# Controller-Board_Rack-PDU.net
KiCad netlist of a schematic drawn in EAGLE
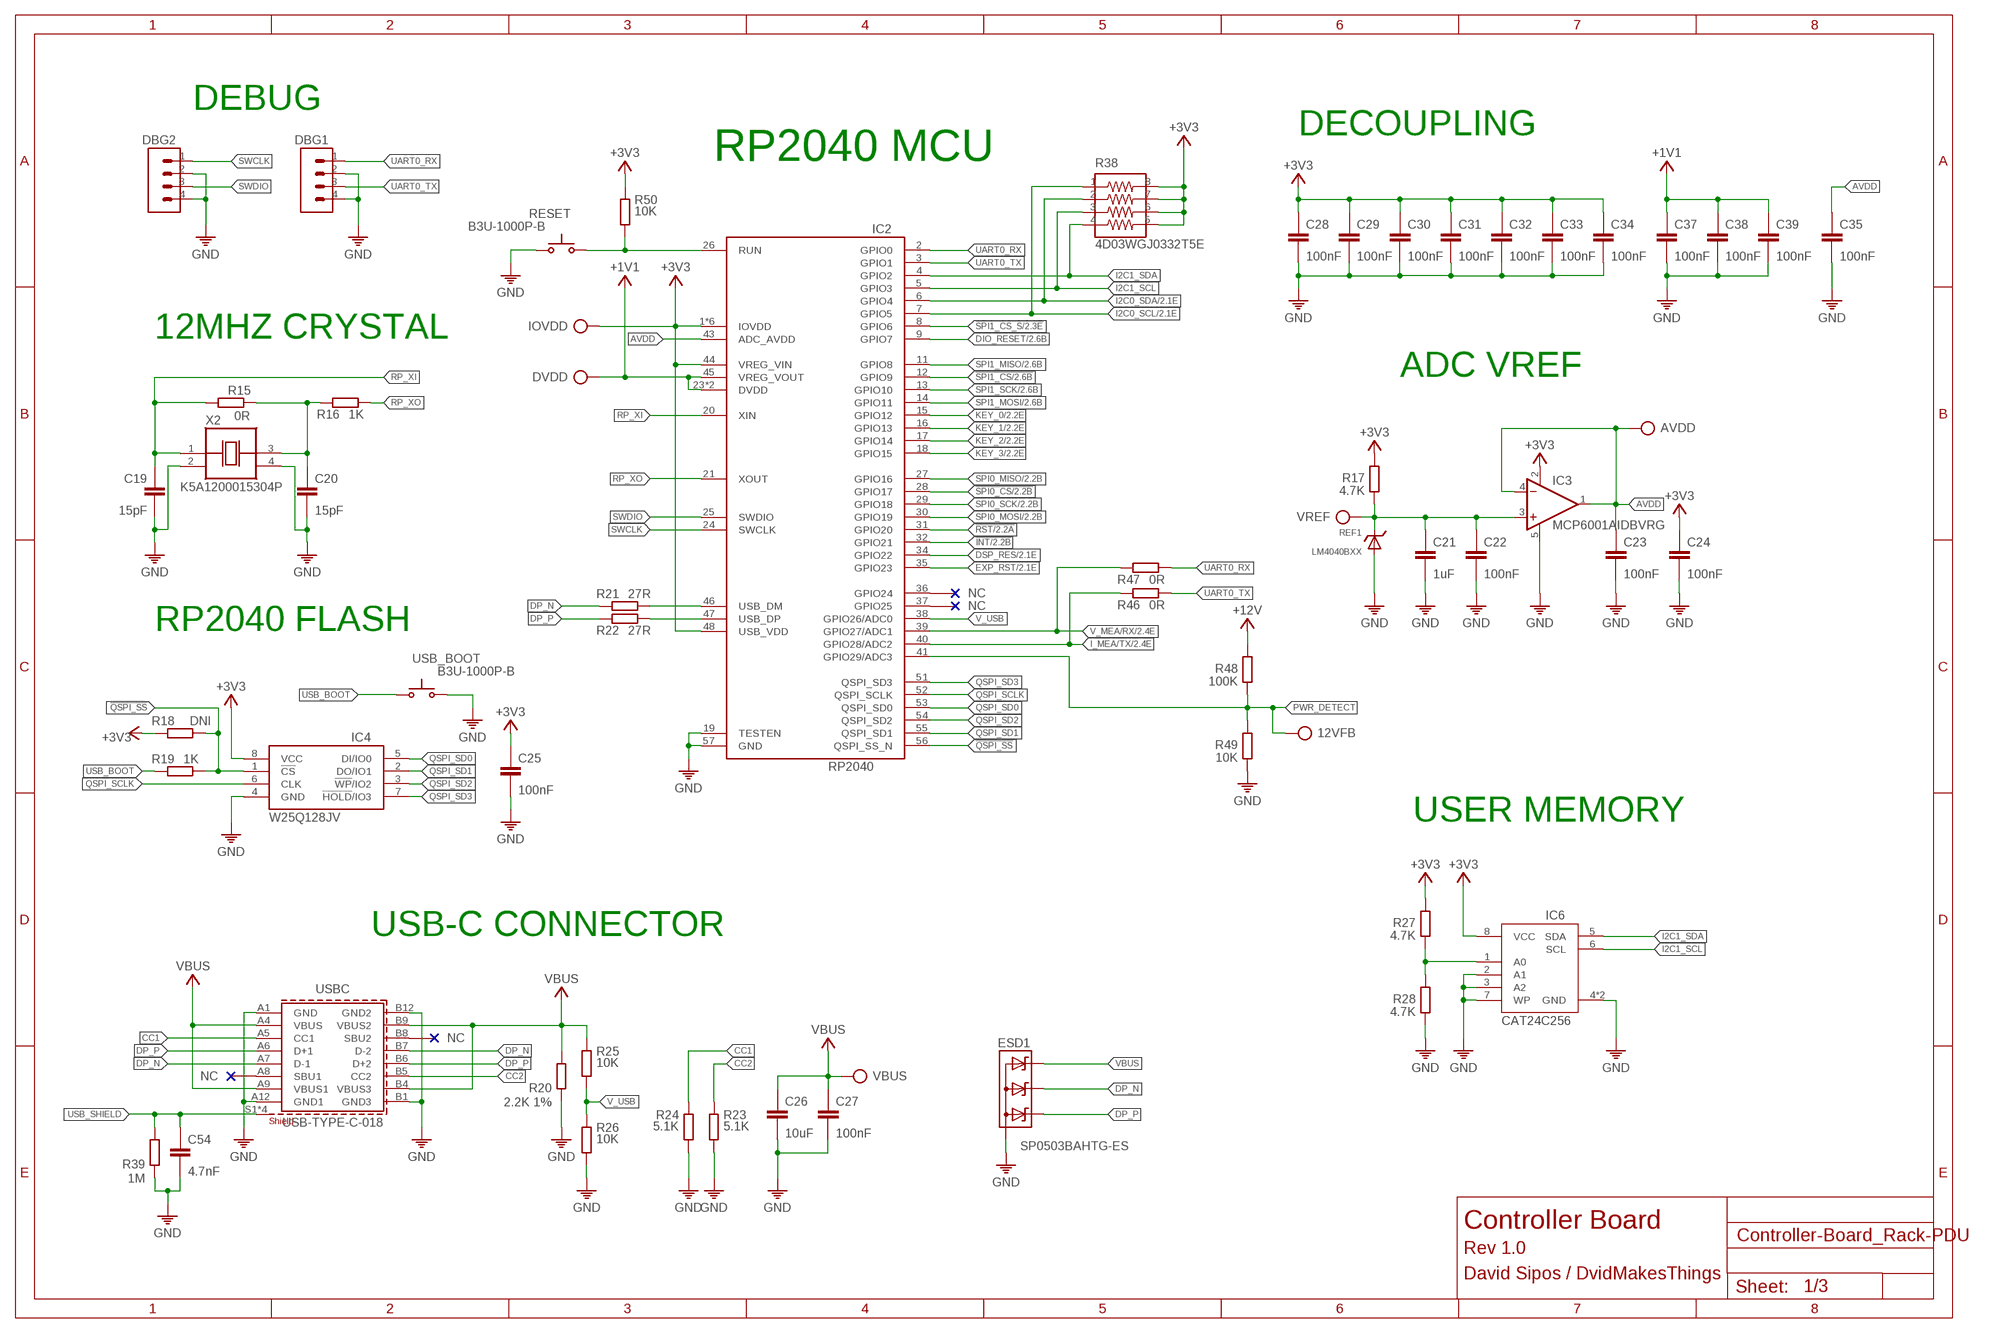
[diagram p0: schematic, sheet 1]
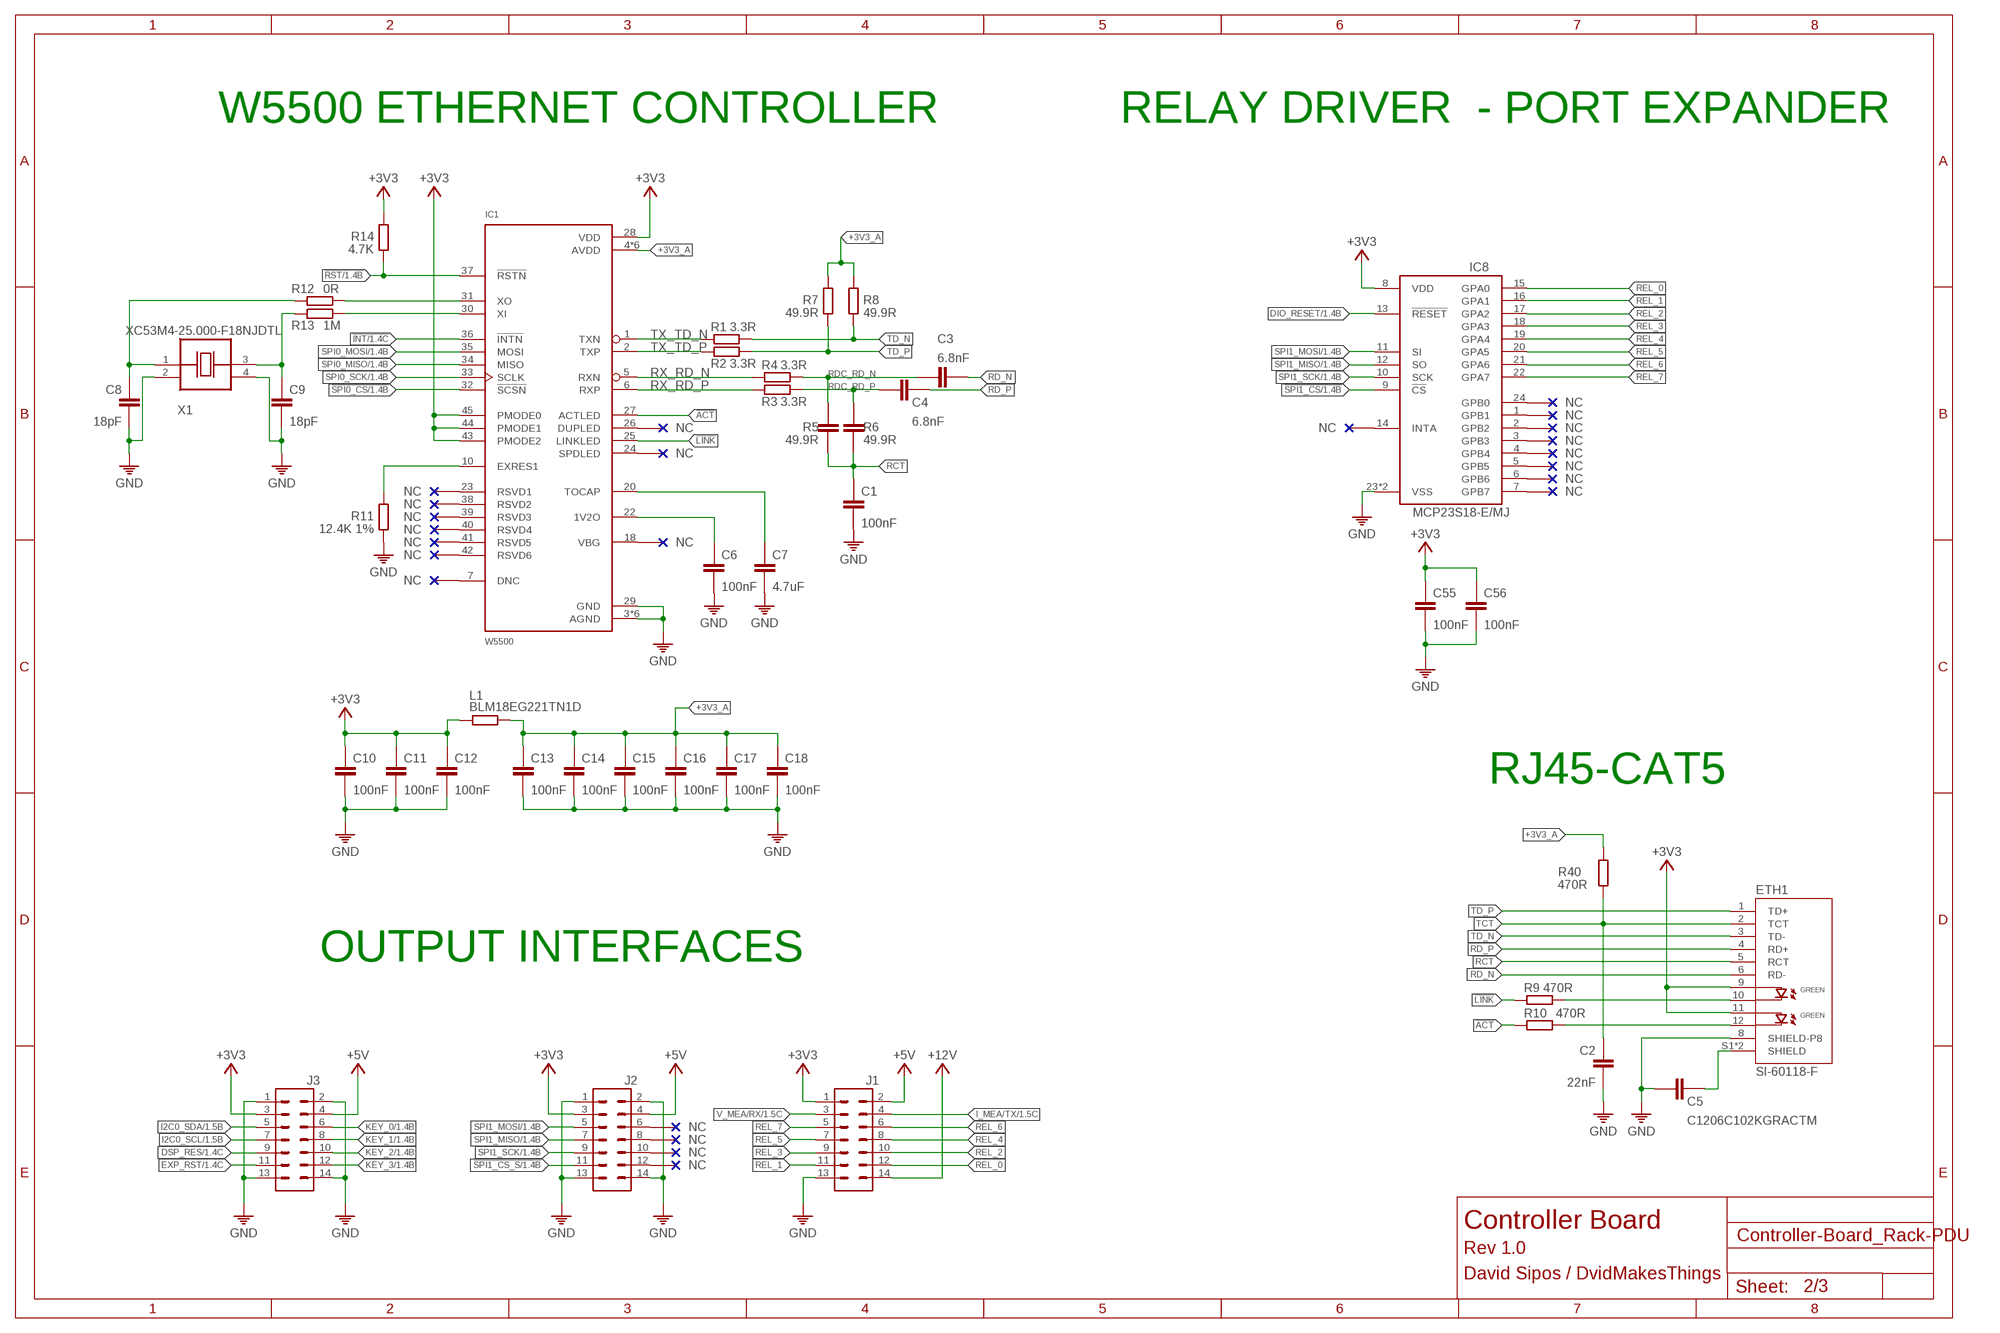
[diagram p1: schematic, sheet 2]
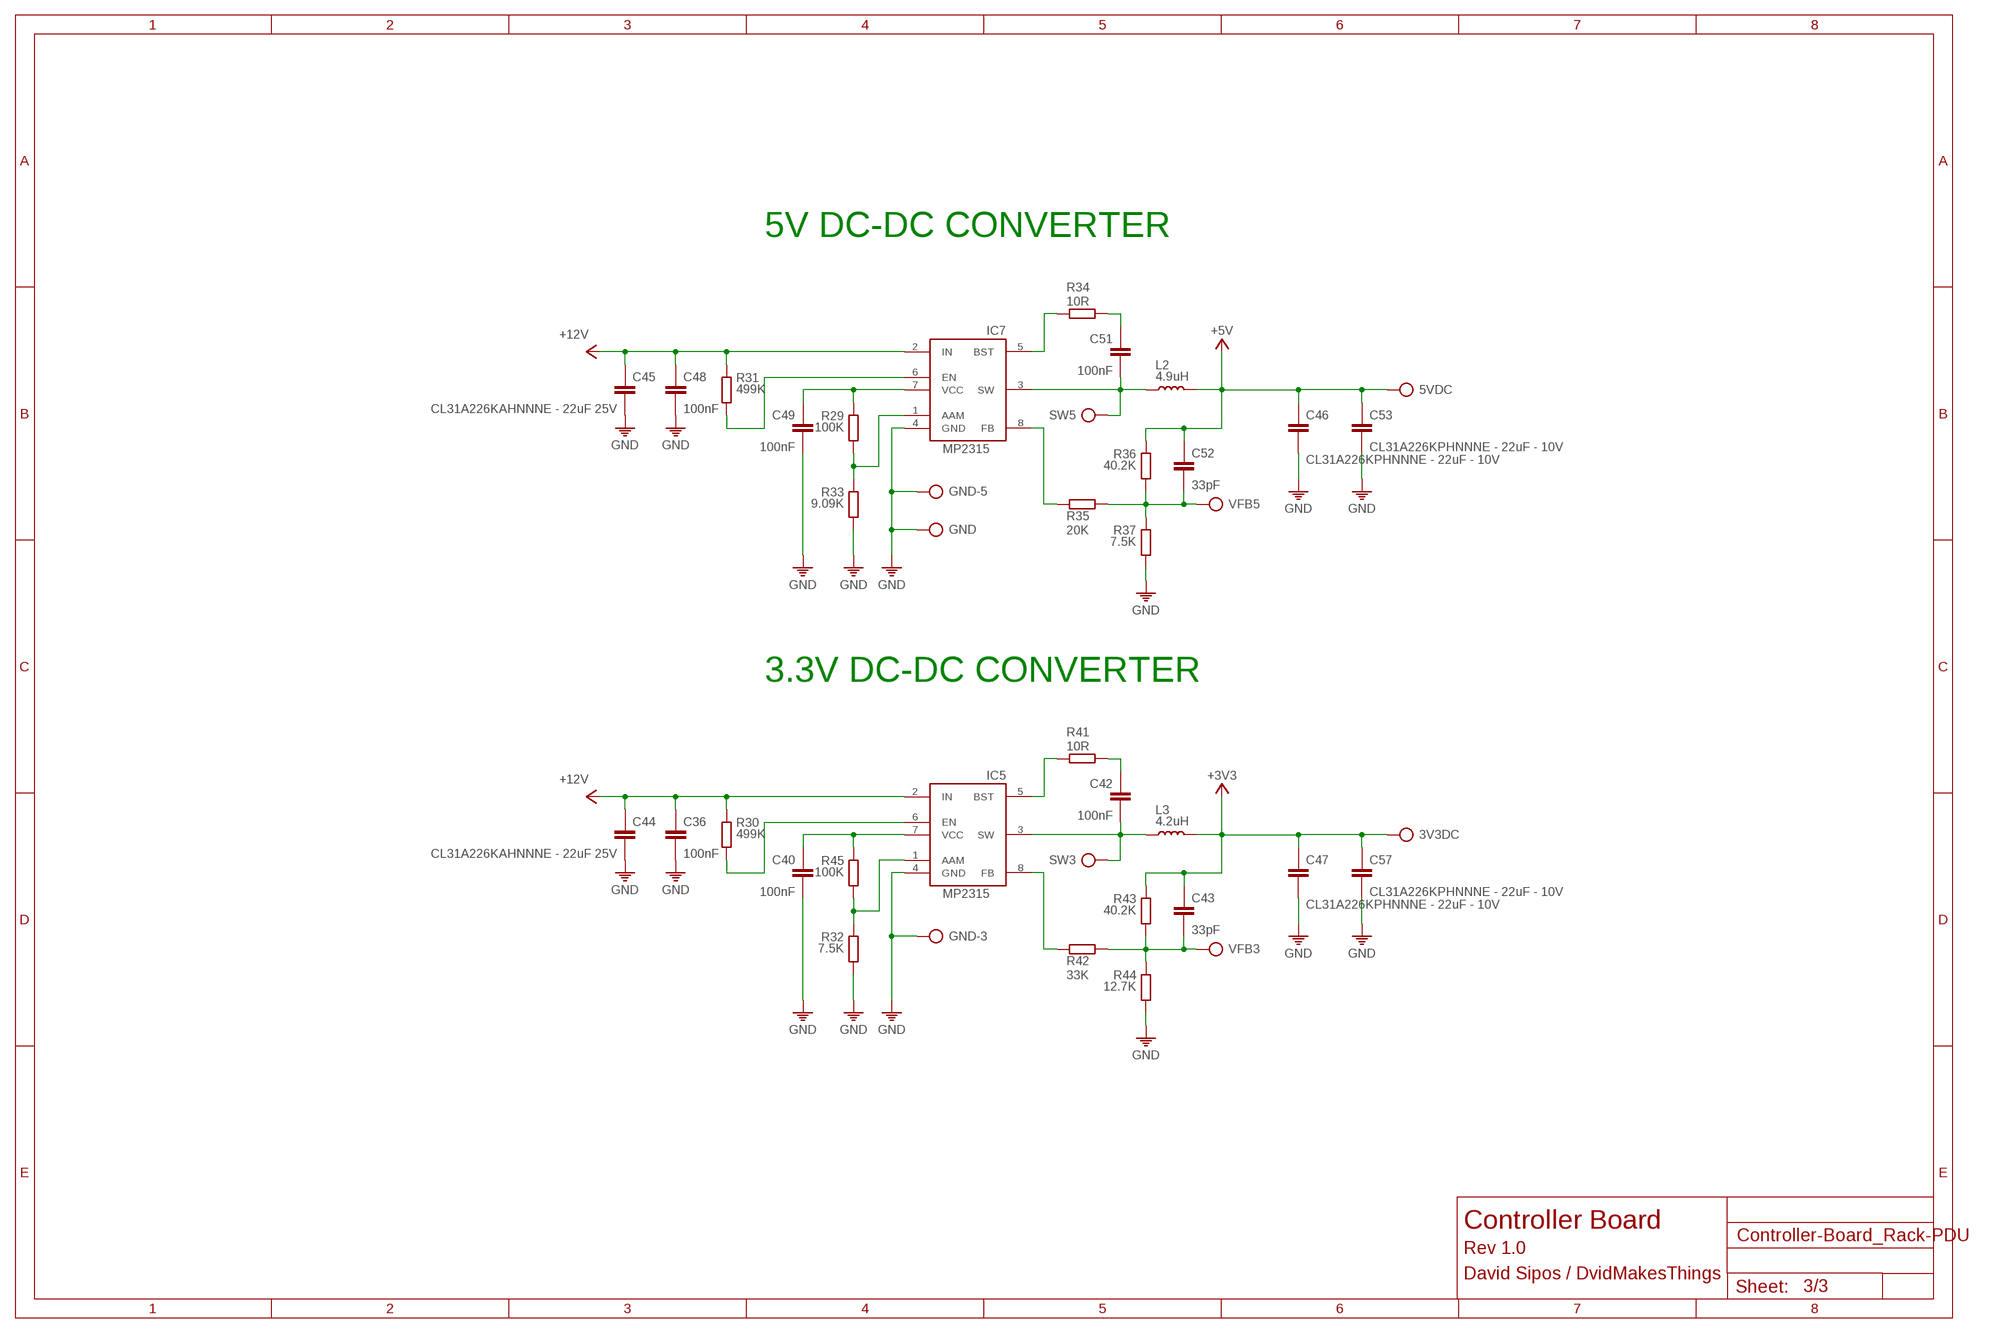
[diagram p2: schematic, sheet 3]

(export (version "E")
  (design (tool "Eeschema 10.0.6"))
  (components
    (comp (ref "12VFB")
      (value "TP")
      (footprint "eagle-import:TP")
      (libsource (lib "eagle-import") (part "TP"))
    )
    (comp (ref "AVDD")
      (value "TP")
      (footprint "eagle-import:TP")
      (libsource (lib "eagle-import") (part "TP"))
    )
    (comp (ref "C19")
      (value "15pF")
      (footprint "eagle-import:C0402")
      (libsource (lib "eagle-import") (part "C-0402"))
    )
    (comp (ref "C20")
      (value "15pF")
      (footprint "eagle-import:C0402")
      (libsource (lib "eagle-import") (part "C-0402"))
    )
    (comp (ref "C21")
      (value "1uF")
      (footprint "eagle-import:C0402")
      (libsource (lib "eagle-import") (part "C-0402"))
    )
    (comp (ref "C22")
      (value "100nF")
      (footprint "eagle-import:C0402")
      (libsource (lib "eagle-import") (part "C-0402"))
    )
    (comp (ref "C23")
      (value "100nF")
      (footprint "eagle-import:C0402")
      (libsource (lib "eagle-import") (part "C-0402"))
    )
    (comp (ref "C24")
      (value "100nF")
      (footprint "eagle-import:C0402")
      (libsource (lib "eagle-import") (part "C-0402"))
    )
    (comp (ref "C25")
      (value "100nF")
      (footprint "eagle-import:C0402")
      (libsource (lib "eagle-import") (part "C-0402"))
    )
    (comp (ref "C26")
      (value "10uF")
      (footprint "eagle-import:0805")
      (libsource (lib "eagle-import") (part "C0805"))
    )
    (comp (ref "C27")
      (value "100nF")
      (footprint "eagle-import:0402")
      (libsource (lib "eagle-import") (part "C0402"))
    )
    (comp (ref "C28")
      (value "100nF")
      (footprint "eagle-import:C0402")
      (libsource (lib "eagle-import") (part "C-0402"))
    )
    (comp (ref "C29")
      (value "100nF")
      (footprint "eagle-import:C0402")
      (libsource (lib "eagle-import") (part "C-0402"))
    )
    (comp (ref "C30")
      (value "100nF")
      (footprint "eagle-import:C0402")
      (libsource (lib "eagle-import") (part "C-0402"))
    )
    (comp (ref "C31")
      (value "100nF")
      (footprint "eagle-import:C0402")
      (libsource (lib "eagle-import") (part "C-0402"))
    )
    (comp (ref "C32")
      (value "100nF")
      (footprint "eagle-import:C0402")
      (libsource (lib "eagle-import") (part "C-0402"))
    )
    (comp (ref "C33")
      (value "100nF")
      (footprint "eagle-import:C0402")
      (libsource (lib "eagle-import") (part "C-0402"))
    )
    (comp (ref "C34")
      (value "100nF")
      (footprint "eagle-import:C0402")
      (libsource (lib "eagle-import") (part "C-0402"))
    )
    (comp (ref "C35")
      (value "100nF")
      (footprint "eagle-import:C0402")
      (libsource (lib "eagle-import") (part "C-0402"))
    )
    (comp (ref "C37")
      (value "100nF")
      (footprint "eagle-import:C0402")
      (libsource (lib "eagle-import") (part "C-0402"))
    )
    (comp (ref "C38")
      (value "100nF")
      (footprint "eagle-import:C0402")
      (libsource (lib "eagle-import") (part "C-0402"))
    )
    (comp (ref "C39")
      (value "100nF")
      (footprint "eagle-import:C0402")
      (libsource (lib "eagle-import") (part "C-0402"))
    )
    (comp (ref "C54")
      (value "4.7nF")
      (footprint "eagle-import:0402")
      (libsource (lib "eagle-import") (part "C0402"))
    )
    (comp (ref "DBG1")
      (value "CON-1X4")
      (footprint "eagle-import:1X4")
      (libsource (lib "eagle-import") (part "CON-1X4"))
    )
    (comp (ref "DBG2")
      (value "CON-1X4")
      (footprint "eagle-import:1X4")
      (libsource (lib "eagle-import") (part "CON-1X4"))
    )
    (comp (ref "DVDD")
      (value "TP")
      (footprint "eagle-import:TP")
      (libsource (lib "eagle-import") (part "TP"))
    )
    (comp (ref "ESD1")
      (value "SP0503BAHTG-ES")
      (footprint "eagle-import:SOT143")
      (libsource (lib "eagle-import") (part "SP0503BAHT"))
    )
    (comp (ref "IC2")
      (value "RP2040")
      (footprint "eagle-import:QFN40P700X700X100-57T510")
      (libsource (lib "eagle-import") (part "RP2040"))
    )
    (comp (ref "IC3")
      (value "MCP6001AIDBVRG")
      (footprint "eagle-import:SOT23-5")
      (libsource (lib "eagle-import") (part "MCP6001RT"))
    )
    (comp (ref "IC4")
      (value "W25Q128JVPIQ")
      (footprint "eagle-import:SON127P600X500X75-8N")
      (libsource (lib "eagle-import") (part "W25Q128JVP"))
    )
    (comp (ref "IC6")
      (value "CAT24C256HU4IGT3")
      (footprint "eagle-import:SON50P300X200X50-9T130X140N")
      (libsource (lib "eagle-import") (part "CAT24C256-HU4"))
    )
    (comp (ref "IOVDD")
      (value "TP")
      (footprint "eagle-import:TP")
      (libsource (lib "eagle-import") (part "TP"))
    )
    (comp (ref "R15")
      (value "0R")
      (footprint "eagle-import:0402")
      (libsource (lib "eagle-import") (part "R0402"))
    )
    (comp (ref "R16")
      (value "1K")
      (footprint "eagle-import:0402")
      (libsource (lib "eagle-import") (part "R0402"))
    )
    (comp (ref "R17")
      (value "4.7K")
      (footprint "eagle-import:0402")
      (libsource (lib "eagle-import") (part "R0402"))
    )
    (comp (ref "R18")
      (value "DNI")
      (footprint "eagle-import:0402")
      (libsource (lib "eagle-import") (part "R0402"))
    )
    (comp (ref "R19")
      (value "1K")
      (footprint "eagle-import:0402")
      (libsource (lib "eagle-import") (part "R0402"))
    )
    (comp (ref "R20")
      (value "2.2K 1%")
      (footprint "eagle-import:0402")
      (libsource (lib "eagle-import") (part "ds_passive_46685041_R0402"))
    )
    (comp (ref "R21")
      (value "27R")
      (footprint "eagle-import:0402")
      (libsource (lib "eagle-import") (part "R0402"))
    )
    (comp (ref "R22")
      (value "27R")
      (footprint "eagle-import:0402")
      (libsource (lib "eagle-import") (part "R0402"))
    )
    (comp (ref "R23")
      (value "5.1K")
      (footprint "eagle-import:0402")
      (libsource (lib "eagle-import") (part "ds_passive_46685041_R0402"))
    )
    (comp (ref "R24")
      (value "5.1K")
      (footprint "eagle-import:0402")
      (libsource (lib "eagle-import") (part "ds_passive_46685041_R0402"))
    )
    (comp (ref "R25")
      (value "10K")
      (footprint "eagle-import:0402")
      (libsource (lib "eagle-import") (part "ds_passive_46685041_R0402"))
    )
    (comp (ref "R26")
      (value "10K")
      (footprint "eagle-import:0402")
      (libsource (lib "eagle-import") (part "ds_passive_46685041_R0402"))
    )
    (comp (ref "R27")
      (value "4.7K")
      (footprint "eagle-import:0402")
      (libsource (lib "eagle-import") (part "R0402"))
    )
    (comp (ref "R28")
      (value "4.7K")
      (footprint "eagle-import:0402")
      (libsource (lib "eagle-import") (part "R0402"))
    )
    (comp (ref "R38")
      (value "4D03WGJ0332T5E")
      (footprint "eagle-import:742C083103JP")
      (fields
        (field (name "MANUFACTURER") "CTS Resistor Products")
        (field (name "MPN") "742C083103JP")
        (field (name "CREATED_BY") "PCBLayout.com")
      )
      (libsource (lib "eagle-import") (part "742C083103JP"))
    )
    (comp (ref "R39")
      (value "1M")
      (footprint "eagle-import:0402")
      (libsource (lib "eagle-import") (part "ds_passive_46685041_R0402"))
    )
    (comp (ref "R46")
      (value "0R")
      (footprint "eagle-import:0402")
      (libsource (lib "eagle-import") (part "R0402"))
    )
    (comp (ref "R47")
      (value "0R")
      (footprint "eagle-import:0402")
      (libsource (lib "eagle-import") (part "R0402"))
    )
    (comp (ref "R48")
      (value "100K")
      (footprint "eagle-import:0402")
      (libsource (lib "eagle-import") (part "R0402"))
    )
    (comp (ref "R49")
      (value "10K")
      (footprint "eagle-import:0402")
      (libsource (lib "eagle-import") (part "R0402"))
    )
    (comp (ref "R50")
      (value "10K")
      (footprint "eagle-import:0402")
      (libsource (lib "eagle-import") (part "ds_passive_46685041_R0402"))
    )
    (comp (ref "REF1")
      (value "LM4040BXX")
      (footprint "eagle-import:SOT23")
      (libsource (lib "eagle-import") (part "LM4040BXX"))
    )
    (comp (ref "RESET")
      (value "B3U-1000P-B")
      (footprint "eagle-import:SWITCH-OMRON_B3U-1000P")
      (libsource (lib "eagle-import") (part "SWITCH-OMRON_B3U-1000P"))
    )
    (comp (ref "USBC")
      (value "USB-TYPE-C-018")
      (footprint "eagle-import:629722000214")
      (libsource (lib "eagle-import") (part "629722000214"))
    )
    (comp (ref "USB_BOOT")
      (value "B3U-1000P-B")
      (footprint "eagle-import:SWITCH-OMRON_B3U-1000P")
      (libsource (lib "eagle-import") (part "SWITCH-OMRON_B3U-1000P"))
    )
    (comp (ref "VBUS")
      (value "TP")
      (footprint "eagle-import:TP")
      (libsource (lib "eagle-import") (part "TP"))
    )
    (comp (ref "VREF")
      (value "TP")
      (footprint "eagle-import:TP")
      (libsource (lib "eagle-import") (part "TP"))
    )
    (comp (ref "X2")
      (value "K5A1200015304P")
      (footprint "eagle-import:OSCCC500X320X130")
      (libsource (lib "eagle-import") (part "CRYSTAL"))
    )
    (comp (ref "3V3DC")
      (value "TP")
      (footprint "eagle-import:TP")
      (libsource (lib "eagle-import") (part "TP"))
    )
    (comp (ref "5VDC")
      (value "TP")
      (footprint "eagle-import:TP")
      (libsource (lib "eagle-import") (part "TP"))
    )
    (comp (ref "C36")
      (value "100nF")
      (footprint "eagle-import:0402")
      (libsource (lib "eagle-import") (part "C0402"))
    )
    (comp (ref "C40")
      (value "100nF")
      (footprint "eagle-import:0402")
      (libsource (lib "eagle-import") (part "C0402"))
    )
    (comp (ref "C42")
      (value "100nF")
      (footprint "eagle-import:0402")
      (libsource (lib "eagle-import") (part "C0402"))
    )
    (comp (ref "C43")
      (value "33pF")
      (footprint "eagle-import:0402")
      (libsource (lib "eagle-import") (part "C0402"))
    )
    (comp (ref "C44")
      (value "CL31A226KAHNNNE - 22uF 25V")
      (footprint "eagle-import:C1206")
      (libsource (lib "eagle-import") (part "C-1206"))
    )
    (comp (ref "C45")
      (value "CL31A226KAHNNNE - 22uF 25V")
      (footprint "eagle-import:C1206")
      (libsource (lib "eagle-import") (part "C-1206"))
    )
    (comp (ref "C46")
      (value "CL31A226KPHNNNE - 22uF - 10V")
      (footprint "eagle-import:C1206")
      (libsource (lib "eagle-import") (part "C-1206"))
    )
    (comp (ref "C47")
      (value "CL31A226KPHNNNE - 22uF - 10V")
      (footprint "eagle-import:C1206")
      (libsource (lib "eagle-import") (part "C-1206"))
    )
    (comp (ref "C48")
      (value "100nF")
      (footprint "eagle-import:0402")
      (libsource (lib "eagle-import") (part "C0402"))
    )
    (comp (ref "C49")
      (value "100nF")
      (footprint "eagle-import:0402")
      (libsource (lib "eagle-import") (part "C0402"))
    )
    (comp (ref "C51")
      (value "100nF")
      (footprint "eagle-import:0402")
      (libsource (lib "eagle-import") (part "C0402"))
    )
    (comp (ref "C52")
      (value "33pF")
      (footprint "eagle-import:0402")
      (libsource (lib "eagle-import") (part "C0402"))
    )
    (comp (ref "C53")
      (value "CL31A226KPHNNNE - 22uF - 10V")
      (footprint "eagle-import:C1206")
      (libsource (lib "eagle-import") (part "C-1206"))
    )
    (comp (ref "C57")
      (value "CL31A226KPHNNNE - 22uF - 10V")
      (footprint "eagle-import:C1206")
      (libsource (lib "eagle-import") (part "C-1206"))
    )
    (comp (ref "GND") (value "TP") (footprint "eagle-import:TP") (libsource (lib "eagle-import") (part "TP")))
    (comp (ref "GND-3")
      (value "TP")
      (footprint "eagle-import:TP")
      (libsource (lib "eagle-import") (part "TP"))
    )
    (comp (ref "GND-5")
      (value "TP")
      (footprint "eagle-import:TP")
      (libsource (lib "eagle-import") (part "TP"))
    )
    (comp (ref "IC5")
      (value "MP2315S")
      (footprint "eagle-import:SOT65P280X110-8N")
      (libsource (lib "eagle-import") (part "MP2315TSOT23-8"))
    )
    (comp (ref "IC7")
      (value "MP2315GJ-Z")
      (footprint "eagle-import:SOT65P280X110-8N")
      (libsource (lib "eagle-import") (part "MP2315TSOT23-8"))
    )
    (comp (ref "L2")
      (value "4.9uH")
      (footprint "eagle-import:SRR5228A")
      (libsource (lib "eagle-import") (part "L"))
    )
    (comp (ref "L3")
      (value "4.2uH")
      (footprint "eagle-import:SRR5228A")
      (libsource (lib "eagle-import") (part "L"))
    )
    (comp (ref "R29")
      (value "100K")
      (footprint "eagle-import:0402")
      (libsource (lib "eagle-import") (part "R0402"))
    )
    (comp (ref "R30")
      (value "499K")
      (footprint "eagle-import:0402")
      (libsource (lib "eagle-import") (part "R0402"))
    )
    (comp (ref "R31")
      (value "499K")
      (footprint "eagle-import:0402")
      (libsource (lib "eagle-import") (part "R0402"))
    )
    (comp (ref "R32")
      (value "7.5K")
      (footprint "eagle-import:0402")
      (libsource (lib "eagle-import") (part "R0402"))
    )
    (comp (ref "R33")
      (value "9.09K")
      (footprint "eagle-import:0402")
      (libsource (lib "eagle-import") (part "R0402"))
    )
    (comp (ref "R34")
      (value "10R")
      (footprint "eagle-import:0402")
      (libsource (lib "eagle-import") (part "R0402"))
    )
    (comp (ref "R35")
      (value "20K")
      (footprint "eagle-import:0402")
      (libsource (lib "eagle-import") (part "R0402"))
    )
    (comp (ref "R36")
      (value "40.2K")
      (footprint "eagle-import:0402")
      (libsource (lib "eagle-import") (part "R0402"))
    )
    (comp (ref "R37")
      (value "7.5K")
      (footprint "eagle-import:0402")
      (libsource (lib "eagle-import") (part "R0402"))
    )
    (comp (ref "R41")
      (value "10R")
      (footprint "eagle-import:0402")
      (libsource (lib "eagle-import") (part "R0402"))
    )
    (comp (ref "R42")
      (value "33K")
      (footprint "eagle-import:0402")
      (libsource (lib "eagle-import") (part "R0402"))
    )
    (comp (ref "R43")
      (value "40.2K")
      (footprint "eagle-import:0402")
      (libsource (lib "eagle-import") (part "R0402"))
    )
    (comp (ref "R44")
      (value "12.7K")
      (footprint "eagle-import:0402")
      (libsource (lib "eagle-import") (part "R0402"))
    )
    (comp (ref "R45")
      (value "100K")
      (footprint "eagle-import:0402")
      (libsource (lib "eagle-import") (part "R0402"))
    )
    (comp (ref "SW3") (value "TP") (footprint "eagle-import:TP") (libsource (lib "eagle-import") (part "TP")))
    (comp (ref "SW5") (value "TP") (footprint "eagle-import:TP") (libsource (lib "eagle-import") (part "TP")))
    (comp (ref "VFB3")
      (value "TP")
      (footprint "eagle-import:TP")
      (libsource (lib "eagle-import") (part "TP"))
    )
    (comp (ref "VFB5")
      (value "TP")
      (footprint "eagle-import:TP")
      (libsource (lib "eagle-import") (part "TP"))
    )
    (comp (ref "C1")
      (value "100nF")
      (footprint "eagle-import:C0402")
      (libsource (lib "eagle-import") (part "C-0402"))
    )
    (comp (ref "C2")
      (value "22nF")
      (footprint "eagle-import:C0402")
      (libsource (lib "eagle-import") (part "C-0402"))
    )
    (comp (ref "C3")
      (value "6.8nF")
      (footprint "eagle-import:C0402")
      (libsource (lib "eagle-import") (part "C-0402"))
    )
    (comp (ref "C4")
      (value "6.8nF")
      (footprint "eagle-import:C0402")
      (libsource (lib "eagle-import") (part "C-0402"))
    )
    (comp (ref "C5")
      (value "C1206C102KGRACTM")
      (footprint "eagle-import:C1206")
      (libsource (lib "eagle-import") (part "C-1206"))
    )
    (comp (ref "C6")
      (value "100nF")
      (footprint "eagle-import:C0402")
      (libsource (lib "eagle-import") (part "C-0402"))
    )
    (comp (ref "C7")
      (value "4.7uF")
      (footprint "eagle-import:C0402")
      (libsource (lib "eagle-import") (part "C-0402"))
    )
    (comp (ref "C8")
      (value "18pF")
      (footprint "eagle-import:C0402")
      (libsource (lib "eagle-import") (part "C-0402"))
    )
    (comp (ref "C9")
      (value "18pF")
      (footprint "eagle-import:C0402")
      (libsource (lib "eagle-import") (part "C-0402"))
    )
    (comp (ref "C10")
      (value "100nF")
      (footprint "eagle-import:C0402")
      (libsource (lib "eagle-import") (part "C-0402"))
    )
    (comp (ref "C11")
      (value "100nF")
      (footprint "eagle-import:C0402")
      (libsource (lib "eagle-import") (part "C-0402"))
    )
    (comp (ref "C12")
      (value "100nF")
      (footprint "eagle-import:C0402")
      (libsource (lib "eagle-import") (part "C-0402"))
    )
    (comp (ref "C13")
      (value "100nF")
      (footprint "eagle-import:C0402")
      (libsource (lib "eagle-import") (part "C-0402"))
    )
    (comp (ref "C14")
      (value "100nF")
      (footprint "eagle-import:C0402")
      (libsource (lib "eagle-import") (part "C-0402"))
    )
    (comp (ref "C15")
      (value "100nF")
      (footprint "eagle-import:C0402")
      (libsource (lib "eagle-import") (part "C-0402"))
    )
    (comp (ref "C16")
      (value "100nF")
      (footprint "eagle-import:C0402")
      (libsource (lib "eagle-import") (part "C-0402"))
    )
    (comp (ref "C17")
      (value "100nF")
      (footprint "eagle-import:C0402")
      (libsource (lib "eagle-import") (part "C-0402"))
    )
    (comp (ref "C18")
      (value "100nF")
      (footprint "eagle-import:C0402")
      (libsource (lib "eagle-import") (part "C-0402"))
    )
    (comp (ref "C55")
      (value "100nF")
      (footprint "eagle-import:C0402")
      (libsource (lib "eagle-import") (part "C-0402"))
    )
    (comp (ref "C56")
      (value "100nF")
      (footprint "eagle-import:C0402")
      (libsource (lib "eagle-import") (part "C-0402"))
    )
    (comp (ref "ETH1")
      (value "SI-60118-F")
      (footprint "eagle-import:RJ45-CAT5")
      (fields (field (name "MANUFACTURER") "Bel Fuse"))
      (libsource (lib "eagle-import") (part "RJ45-CAT5"))
    )
    (comp (ref "IC1")
      (value "W5500")
      (footprint "eagle-import:LQFP48")
      (libsource (lib "eagle-import") (part "W5500"))
    )
    (comp (ref "IC8")
      (value "MCP23S18-E/MJ")
      (footprint "eagle-import:QFN50P400X400X100-25T265")
      (libsource (lib "eagle-import") (part "MCP23S18"))
    )
    (comp (ref "J1")
      (value "CON-2X7")
      (footprint "eagle-import:2X7")
      (libsource (lib "eagle-import") (part "CON-2X7"))
    )
    (comp (ref "J2")
      (value "CON-2X7")
      (footprint "eagle-import:2X7")
      (libsource (lib "eagle-import") (part "CON-2X7"))
    )
    (comp (ref "J3")
      (value "CON-2X7")
      (footprint "eagle-import:2X7")
      (libsource (lib "eagle-import") (part "CON-2X7"))
    )
    (comp (ref "L1")
      (value "BLM18EG221TN1D")
      (footprint "eagle-import:0603")
      (libsource (lib "eagle-import") (part "R0603"))
    )
    (comp (ref "R1")
      (value "3.3R")
      (footprint "eagle-import:0402")
      (libsource (lib "eagle-import") (part "R0402"))
    )
    (comp (ref "R2")
      (value "3.3R")
      (footprint "eagle-import:0402")
      (libsource (lib "eagle-import") (part "R0402"))
    )
    (comp (ref "R3")
      (value "3.3R")
      (footprint "eagle-import:0402")
      (libsource (lib "eagle-import") (part "R0402"))
    )
    (comp (ref "R4")
      (value "3.3R")
      (footprint "eagle-import:0402")
      (libsource (lib "eagle-import") (part "R0402"))
    )
    (comp (ref "R5")
      (value "49.9R")
      (footprint "eagle-import:C0402")
      (libsource (lib "eagle-import") (part "C-0402"))
    )
    (comp (ref "R6")
      (value "49.9R")
      (footprint "eagle-import:C0402")
      (libsource (lib "eagle-import") (part "C-0402"))
    )
    (comp (ref "R7")
      (value "49.9R")
      (footprint "eagle-import:0402")
      (libsource (lib "eagle-import") (part "R0402"))
    )
    (comp (ref "R8")
      (value "49.9R")
      (footprint "eagle-import:0402")
      (libsource (lib "eagle-import") (part "R0402"))
    )
    (comp (ref "R9")
      (value "470R")
      (footprint "eagle-import:0402")
      (libsource (lib "eagle-import") (part "R0402"))
    )
    (comp (ref "R10")
      (value "470R")
      (footprint "eagle-import:0402")
      (libsource (lib "eagle-import") (part "R0402"))
    )
    (comp (ref "R11")
      (value "12.4K 1%")
      (footprint "eagle-import:0402")
      (libsource (lib "eagle-import") (part "R0402"))
    )
    (comp (ref "R12")
      (value "0R")
      (footprint "eagle-import:0402")
      (libsource (lib "eagle-import") (part "R0402"))
    )
    (comp (ref "R13")
      (value "1M")
      (footprint "eagle-import:0402")
      (libsource (lib "eagle-import") (part "R0402"))
    )
    (comp (ref "R14")
      (value "4.7K")
      (footprint "eagle-import:0402")
      (libsource (lib "eagle-import") (part "R0402"))
    )
    (comp (ref "R40")
      (value "470R")
      (footprint "eagle-import:0402")
      (libsource (lib "eagle-import") (part "R0402"))
    )
    (comp (ref "X1")
      (value "XC53M4-25.000-F18NJDTL")
      (footprint "eagle-import:OSCCC500X320X130")
      (libsource (lib "eagle-import") (part "CRYSTAL"))
    )
  )
  (nets
    (net (code "1") (name "+1V1") (class "Default")
      (node (ref "C37") (pin "1") (pinfunction "1_1") (pintype "passive"))
      (node (ref "C38") (pin "1") (pinfunction "1_1") (pintype "passive"))
      (node (ref "C39") (pin "1") (pinfunction "1_1") (pintype "passive"))
      (node (ref "DVDD") (pin "TP") (pinfunction "P$1_TP") (pintype "bidirectional"))
      (node (ref "IC2") (pin "23") (pinfunction "DVDD_23") (pintype "bidirectional"))
      (node (ref "IC2") (pin "45") (pinfunction "VREG_VOUT_45") (pintype "bidirectional"))
      (node (ref "IC2") (pin "50") (pinfunction "DVDD_50") (pintype "bidirectional"))
    )
    (net (code "2") (name "+3V3") (class "Default")
      (node (ref "3V3DC") (pin "TP") (pinfunction "P$1_TP") (pintype "bidirectional"))
      (node (ref "C10") (pin "1") (pinfunction "1_1") (pintype "passive"))
      (node (ref "C11") (pin "1") (pinfunction "1_1") (pintype "passive"))
      (node (ref "C12") (pin "1") (pinfunction "1_1") (pintype "passive"))
      (node (ref "C24") (pin "1") (pinfunction "1_1") (pintype "passive"))
      (node (ref "C25") (pin "1") (pinfunction "1_1") (pintype "passive"))
      (node (ref "C28") (pin "1") (pinfunction "1_1") (pintype "passive"))
      (node (ref "C29") (pin "1") (pinfunction "1_1") (pintype "passive"))
      (node (ref "C30") (pin "1") (pinfunction "1_1") (pintype "passive"))
      (node (ref "C31") (pin "1") (pinfunction "1_1") (pintype "passive"))
      (node (ref "C32") (pin "1") (pinfunction "1_1") (pintype "passive"))
      (node (ref "C33") (pin "1") (pinfunction "1_1") (pintype "passive"))
      (node (ref "C34") (pin "1") (pinfunction "1_1") (pintype "passive"))
      (node (ref "C43") (pin "1") (pinfunction "1_1") (pintype "passive"))
      (node (ref "C47") (pin "1") (pinfunction "1_1") (pintype "passive"))
      (node (ref "C55") (pin "1") (pinfunction "1_1") (pintype "passive"))
      (node (ref "C56") (pin "1") (pinfunction "1_1") (pintype "passive"))
      (node (ref "C57") (pin "1") (pinfunction "1_1") (pintype "passive"))
      (node (ref "ETH1") (pin "11") (pinfunction "GA2_11") (pintype "passive"))
      (node (ref "ETH1") (pin "9") (pinfunction "GA1_9") (pintype "passive"))
      (node (ref "IC1") (pin "28") (pinfunction "VDD_28") (pintype "power_in"))
      (node (ref "IC1") (pin "43") (pinfunction "PMODE2_43") (pintype "input"))
      (node (ref "IC1") (pin "44") (pinfunction "PMODE1_44") (pintype "input"))
      (node (ref "IC1") (pin "45") (pinfunction "PMODE0_45") (pintype "input"))
      (node (ref "IC2") (pin "1") (pinfunction "IOVDD_1") (pintype "bidirectional"))
      (node (ref "IC2") (pin "10") (pinfunction "IOVDD_10") (pintype "bidirectional"))
      (node (ref "IC2") (pin "22") (pinfunction "IOVDD_22") (pintype "bidirectional"))
      (node (ref "IC2") (pin "33") (pinfunction "IOVDD_33") (pintype "bidirectional"))
      (node (ref "IC2") (pin "42") (pinfunction "IOVDD_42") (pintype "bidirectional"))
      (node (ref "IC2") (pin "44") (pinfunction "VREG_VIN_44") (pintype "bidirectional"))
      (node (ref "IC2") (pin "48") (pinfunction "USB_VDD_48") (pintype "bidirectional"))
      (node (ref "IC2") (pin "49") (pinfunction "IOVDD_49") (pintype "bidirectional"))
      (node (ref "IC3") (pin "2") (pinfunction "V+_2") (pintype "power_in"))
      (node (ref "IC4") (pin "8") (pinfunction "VCC_8") (pintype "power_in"))
      (node (ref "IC6") (pin "8") (pinfunction "VCC_8") (pintype "power_in"))
      (node (ref "IC8") (pin "8") (pinfunction "VDD_8") (pintype "power_in"))
      (node (ref "IOVDD") (pin "TP") (pinfunction "P$1_TP") (pintype "bidirectional"))
      (node (ref "J1") (pin "1") (pinfunction "1_1") (pintype "bidirectional"))
      (node (ref "J2") (pin "3") (pinfunction "3_3") (pintype "bidirectional"))
      (node (ref "J3") (pin "3") (pinfunction "3_3") (pintype "bidirectional"))
      (node (ref "L1") (pin "1") (pinfunction "1_1") (pintype "passive"))
      (node (ref "L3") (pin "2") (pinfunction "2_2") (pintype "passive"))
      (node (ref "R14") (pin "2") (pinfunction "2_2") (pintype "passive"))
      (node (ref "R17") (pin "2") (pinfunction "2_2") (pintype "passive"))
      (node (ref "R18") (pin "2") (pinfunction "2_2") (pintype "passive"))
      (node (ref "R27") (pin "2") (pinfunction "2_2") (pintype "passive"))
      (node (ref "R38") (pin "5") (pinfunction "5_5") (pintype "passive"))
      (node (ref "R38") (pin "6") (pinfunction "6_6") (pintype "passive"))
      (node (ref "R38") (pin "7") (pinfunction "7_7") (pintype "passive"))
      (node (ref "R38") (pin "8") (pinfunction "8_8") (pintype "passive"))
      (node (ref "R43") (pin "1") (pinfunction "1_1") (pintype "passive"))
      (node (ref "R50") (pin "1") (pinfunction "1_1") (pintype "passive"))
    )
    (net (code "3") (name "+3V3_A") (class "Default")
      (node (ref "C13") (pin "1") (pinfunction "1_1") (pintype "passive"))
      (node (ref "C14") (pin "1") (pinfunction "1_1") (pintype "passive"))
      (node (ref "C15") (pin "1") (pinfunction "1_1") (pintype "passive"))
      (node (ref "C16") (pin "1") (pinfunction "1_1") (pintype "passive"))
      (node (ref "C17") (pin "1") (pinfunction "1_1") (pintype "passive"))
      (node (ref "C18") (pin "1") (pinfunction "1_1") (pintype "passive"))
      (node (ref "IC1") (pin "11") (pinfunction "AVDD_11") (pintype "power_in"))
      (node (ref "IC1") (pin "15") (pinfunction "AVDD_15") (pintype "power_in"))
      (node (ref "IC1") (pin "17") (pinfunction "AVDD_17") (pintype "power_in"))
      (node (ref "IC1") (pin "21") (pinfunction "AVDD_21") (pintype "power_in"))
      (node (ref "IC1") (pin "4") (pinfunction "AVDD_4") (pintype "power_in"))
      (node (ref "IC1") (pin "8") (pinfunction "AVDD_8") (pintype "power_in"))
      (node (ref "L1") (pin "2") (pinfunction "2_2") (pintype "passive"))
      (node (ref "R40") (pin "2") (pinfunction "2_2") (pintype "passive"))
      (node (ref "R7") (pin "2") (pinfunction "2_2") (pintype "passive"))
      (node (ref "R8") (pin "2") (pinfunction "2_2") (pintype "passive"))
    )
    (net (code "4") (name "+5V") (class "Default")
      (node (ref "5VDC") (pin "TP") (pinfunction "P$1_TP") (pintype "bidirectional"))
      (node (ref "C46") (pin "1") (pinfunction "1_1") (pintype "passive"))
      (node (ref "C52") (pin "1") (pinfunction "1_1") (pintype "passive"))
      (node (ref "C53") (pin "1") (pinfunction "1_1") (pintype "passive"))
      (node (ref "J1") (pin "2") (pinfunction "2_2") (pintype "bidirectional"))
      (node (ref "J2") (pin "4") (pinfunction "4_4") (pintype "bidirectional"))
      (node (ref "J3") (pin "4") (pinfunction "4_4") (pintype "bidirectional"))
      (node (ref "L2") (pin "2") (pinfunction "2_2") (pintype "passive"))
      (node (ref "R36") (pin "1") (pinfunction "1_1") (pintype "passive"))
    )
    (net (code "5") (name "+12V") (class "Default")
      (node (ref "C36") (pin "1") (pinfunction "1_1") (pintype "passive"))
      (node (ref "C44") (pin "1") (pinfunction "1_1") (pintype "passive"))
      (node (ref "C45") (pin "1") (pinfunction "1_1") (pintype "passive"))
      (node (ref "C48") (pin "1") (pinfunction "1_1") (pintype "passive"))
      (node (ref "IC5") (pin "2") (pinfunction "IN_2") (pintype "bidirectional"))
      (node (ref "IC7") (pin "2") (pinfunction "IN_2") (pintype "bidirectional"))
      (node (ref "J1") (pin "14") (pinfunction "14_14") (pintype "bidirectional"))
      (node (ref "R30") (pin "1") (pinfunction "1_1") (pintype "passive"))
      (node (ref "R31") (pin "1") (pinfunction "1_1") (pintype "passive"))
      (node (ref "R48") (pin "2") (pinfunction "2_2") (pintype "passive"))
    )
    (net (code "6") (name "AVDD") (class "Default")
      (node (ref "AVDD") (pin "TP") (pinfunction "P$1_TP") (pintype "bidirectional"))
      (node (ref "C23") (pin "1") (pinfunction "1_1") (pintype "passive"))
      (node (ref "C35") (pin "1") (pinfunction "1_1") (pintype "passive"))
      (node (ref "IC2") (pin "43") (pinfunction "ADC_AVDD_43") (pintype "bidirectional"))
      (node (ref "IC3") (pin "1") (pinfunction "OUT_1") (pintype "output"))
      (node (ref "IC3") (pin "4") (pinfunction "-IN_4") (pintype "input"))
    )
    (net (code "7") (name "CC1") (class "Default")
      (node (ref "R24") (pin "1") (pinfunction "1_1") (pintype "passive"))
      (node (ref "USBC") (pin "A5") (pinfunction "CC1_A5") (pintype "passive"))
    )
    (net (code "8") (name "CC2") (class "Default")
      (node (ref "R23") (pin "1") (pinfunction "1_1") (pintype "passive"))
      (node (ref "USBC") (pin "B5") (pinfunction "CC2_B5") (pintype "passive"))
    )
    (net (code "9") (name "DIO_RESET") (class "Default")
      (node (ref "IC2") (pin "9") (pinfunction "GPIO7_9") (pintype "bidirectional"))
      (node (ref "IC8") (pin "13") (pinfunction "~{RESET}_13") (pintype "input"))
    )
    (net (code "10") (name "DP_N") (class "Default")
      (node (ref "ESD1") (pin "3") (pinfunction "C2_3") (pintype "bidirectional"))
      (node (ref "R21") (pin "1") (pinfunction "1_1") (pintype "passive"))
      (node (ref "USBC") (pin "A7") (pinfunction "D-1_A7") (pintype "passive"))
      (node (ref "USBC") (pin "B7") (pinfunction "D-2_B7") (pintype "passive"))
    )
    (net (code "11") (name "DP_P") (class "Default")
      (node (ref "ESD1") (pin "2") (pinfunction "C1_2") (pintype "bidirectional"))
      (node (ref "R22") (pin "1") (pinfunction "1_1") (pintype "passive"))
      (node (ref "USBC") (pin "A6") (pinfunction "D+1_A6") (pintype "passive"))
      (node (ref "USBC") (pin "B6") (pinfunction "D+2_B6") (pintype "passive"))
    )
    (net (code "12") (name "DSP_RES") (class "Default")
      (node (ref "IC2") (pin "34") (pinfunction "GPIO22_34") (pintype "bidirectional"))
      (node (ref "J3") (pin "9") (pinfunction "9_9") (pintype "bidirectional"))
    )
    (net (code "13") (name "EXP_RST") (class "Default")
      (node (ref "IC2") (pin "35") (pinfunction "GPIO23_35") (pintype "bidirectional"))
      (node (ref "J3") (pin "11") (pinfunction "11_11") (pintype "bidirectional"))
    )
    (net (code "14") (name "GND") (class "Default")
      (node (ref "C1") (pin "2") (pinfunction "2_2") (pintype "passive"))
      (node (ref "C10") (pin "2") (pinfunction "2_2") (pintype "passive"))
      (node (ref "C11") (pin "2") (pinfunction "2_2") (pintype "passive"))
      (node (ref "C12") (pin "2") (pinfunction "2_2") (pintype "passive"))
      (node (ref "C13") (pin "2") (pinfunction "2_2") (pintype "passive"))
      (node (ref "C14") (pin "2") (pinfunction "2_2") (pintype "passive"))
      (node (ref "C15") (pin "2") (pinfunction "2_2") (pintype "passive"))
      (node (ref "C16") (pin "2") (pinfunction "2_2") (pintype "passive"))
      (node (ref "C17") (pin "2") (pinfunction "2_2") (pintype "passive"))
      (node (ref "C18") (pin "2") (pinfunction "2_2") (pintype "passive"))
      (node (ref "C19") (pin "2") (pinfunction "2_2") (pintype "passive"))
      (node (ref "C2") (pin "2") (pinfunction "2_2") (pintype "passive"))
      (node (ref "C20") (pin "2") (pinfunction "2_2") (pintype "passive"))
      (node (ref "C21") (pin "2") (pinfunction "2_2") (pintype "passive"))
      (node (ref "C22") (pin "2") (pinfunction "2_2") (pintype "passive"))
      (node (ref "C23") (pin "2") (pinfunction "2_2") (pintype "passive"))
      (node (ref "C24") (pin "2") (pinfunction "2_2") (pintype "passive"))
      (node (ref "C25") (pin "2") (pinfunction "2_2") (pintype "passive"))
      (node (ref "C26") (pin "2") (pinfunction "2_2") (pintype "passive"))
      (node (ref "C27") (pin "2") (pinfunction "2_2") (pintype "passive"))
      (node (ref "C28") (pin "2") (pinfunction "2_2") (pintype "passive"))
      (node (ref "C29") (pin "2") (pinfunction "2_2") (pintype "passive"))
      (node (ref "C30") (pin "2") (pinfunction "2_2") (pintype "passive"))
      (node (ref "C31") (pin "2") (pinfunction "2_2") (pintype "passive"))
      (node (ref "C32") (pin "2") (pinfunction "2_2") (pintype "passive"))
      (node (ref "C33") (pin "2") (pinfunction "2_2") (pintype "passive"))
      (node (ref "C34") (pin "2") (pinfunction "2_2") (pintype "passive"))
      (node (ref "C35") (pin "2") (pinfunction "2_2") (pintype "passive"))
      (node (ref "C36") (pin "2") (pinfunction "2_2") (pintype "passive"))
      (node (ref "C37") (pin "2") (pinfunction "2_2") (pintype "passive"))
      (node (ref "C38") (pin "2") (pinfunction "2_2") (pintype "passive"))
      (node (ref "C39") (pin "2") (pinfunction "2_2") (pintype "passive"))
      (node (ref "C40") (pin "2") (pinfunction "2_2") (pintype "passive"))
      (node (ref "C44") (pin "2") (pinfunction "2_2") (pintype "passive"))
      (node (ref "C45") (pin "2") (pinfunction "2_2") (pintype "passive"))
      (node (ref "C46") (pin "2") (pinfunction "2_2") (pintype "passive"))
      (node (ref "C47") (pin "2") (pinfunction "2_2") (pintype "passive"))
      (node (ref "C48") (pin "2") (pinfunction "2_2") (pintype "passive"))
      (node (ref "C49") (pin "2") (pinfunction "2_2") (pintype "passive"))
      (node (ref "C5") (pin "1") (pinfunction "1_1") (pintype "passive"))
      (node (ref "C53") (pin "2") (pinfunction "2_2") (pintype "passive"))
      (node (ref "C54") (pin "2") (pinfunction "2_2") (pintype "passive"))
      (node (ref "C55") (pin "2") (pinfunction "2_2") (pintype "passive"))
      (node (ref "C56") (pin "2") (pinfunction "2_2") (pintype "passive"))
      (node (ref "C57") (pin "2") (pinfunction "2_2") (pintype "passive"))
      (node (ref "C6") (pin "2") (pinfunction "2_2") (pintype "passive"))
      (node (ref "C7") (pin "2") (pinfunction "2_2") (pintype "passive"))
      (node (ref "C8") (pin "2") (pinfunction "2_2") (pintype "passive"))
      (node (ref "C9") (pin "2") (pinfunction "2_2") (pintype "passive"))
      (node (ref "DBG1") (pin "2") (pinfunction "P$2_2") (pintype "bidirectional"))
      (node (ref "DBG1") (pin "4") (pinfunction "P$4_4") (pintype "bidirectional"))
      (node (ref "DBG2") (pin "2") (pinfunction "P$2_2") (pintype "bidirectional"))
      (node (ref "DBG2") (pin "4") (pinfunction "P$4_4") (pintype "bidirectional"))
      (node (ref "ESD1") (pin "1") (pinfunction "A_1") (pintype "bidirectional"))
      (node (ref "ETH1") (pin "8") (pinfunction "SHIELD-P8_8") (pintype "passive"))
      (node (ref "GND") (pin "TP") (pinfunction "P$1_TP") (pintype "bidirectional"))
      (node (ref "GND-3") (pin "TP") (pinfunction "P$1_TP") (pintype "bidirectional"))
      (node (ref "GND-5") (pin "TP") (pinfunction "P$1_TP") (pintype "bidirectional"))
      (node (ref "IC1") (pin "14") (pinfunction "AGND_14") (pintype "power_in"))
      (node (ref "IC1") (pin "16") (pinfunction "AGND_16") (pintype "power_in"))
      (node (ref "IC1") (pin "19") (pinfunction "AGND_19") (pintype "power_in"))
      (node (ref "IC1") (pin "29") (pinfunction "GND_29") (pintype "passive"))
      (node (ref "IC1") (pin "3") (pinfunction "AGND_3") (pintype "power_in"))
      (node (ref "IC1") (pin "48") (pinfunction "AGND_48") (pintype "power_in"))
      (node (ref "IC1") (pin "9") (pinfunction "AGND_9") (pintype "power_in"))
      (node (ref "IC2") (pin "19") (pinfunction "TESTEN_19") (pintype "bidirectional"))
      (node (ref "IC2") (pin "57") (pinfunction "GND_57") (pintype "bidirectional"))
      (node (ref "IC3") (pin "5") (pinfunction "V-_5") (pintype "power_in"))
      (node (ref "IC4") (pin "4") (pinfunction "GND_4") (pintype "power_in"))
      (node (ref "IC5") (pin "4") (pinfunction "GND_4") (pintype "bidirectional"))
      (node (ref "IC6") (pin "2") (pinfunction "A1_2") (pintype "bidirectional"))
      (node (ref "IC6") (pin "3") (pinfunction "A2_3") (pintype "bidirectional"))
      (node (ref "IC6") (pin "4") (pinfunction "GND_4") (pintype "power_in"))
      (node (ref "IC6") (pin "7") (pinfunction "WP_7") (pintype "bidirectional"))
      (node (ref "IC6") (pin "9") (pinfunction "GND_9") (pintype "power_in"))
      (node (ref "IC7") (pin "4") (pinfunction "GND_4") (pintype "bidirectional"))
      (node (ref "IC8") (pin "23") (pinfunction "VSS_23") (pintype "power_in"))
      (node (ref "IC8") (pin "25") (pinfunction "VSS_25") (pintype "power_in"))
      (node (ref "J1") (pin "13") (pinfunction "13_13") (pintype "bidirectional"))
      (node (ref "J2") (pin "1") (pinfunction "1_1") (pintype "bidirectional"))
      (node (ref "J2") (pin "13") (pinfunction "13_13") (pintype "bidirectional"))
      (node (ref "J2") (pin "14") (pinfunction "14_14") (pintype "bidirectional"))
      (node (ref "J2") (pin "2") (pinfunction "2_2") (pintype "bidirectional"))
      (node (ref "J3") (pin "1") (pinfunction "1_1") (pintype "bidirectional"))
      (node (ref "J3") (pin "13") (pinfunction "13_13") (pintype "bidirectional"))
      (node (ref "J3") (pin "14") (pinfunction "14_14") (pintype "bidirectional"))
      (node (ref "J3") (pin "2") (pinfunction "2_2") (pintype "bidirectional"))
      (node (ref "R11") (pin "1") (pinfunction "1_1") (pintype "passive"))
      (node (ref "R20") (pin "2") (pinfunction "2_2") (pintype "passive"))
      (node (ref "R23") (pin "2") (pinfunction "2_2") (pintype "passive"))
      (node (ref "R24") (pin "2") (pinfunction "2_2") (pintype "passive"))
      (node (ref "R26") (pin "2") (pinfunction "2_2") (pintype "passive"))
      (node (ref "R28") (pin "1") (pinfunction "1_1") (pintype "passive"))
      (node (ref "R32") (pin "2") (pinfunction "2_2") (pintype "passive"))
      (node (ref "R33") (pin "2") (pinfunction "2_2") (pintype "passive"))
      (node (ref "R37") (pin "2") (pinfunction "2_2") (pintype "passive"))
      (node (ref "R39") (pin "2") (pinfunction "2_2") (pintype "passive"))
      (node (ref "R44") (pin "2") (pinfunction "2_2") (pintype "passive"))
      (node (ref "R49") (pin "1") (pinfunction "1_1") (pintype "passive"))
      (node (ref "REF1") (pin "2") (pinfunction "A_2") (pintype "passive"))
      (node (ref "REF1") (pin "3") (pinfunction "A_3") (pintype "passive"))
      (node (ref "RESET") (pin "2") (pinfunction "S_2") (pintype "passive"))
      (node (ref "USBC") (pin "A1") (pinfunction "GND_A1") (pintype "passive"))
      (node (ref "USBC") (pin "A12") (pinfunction "GND1_A12") (pintype "passive"))
      (node (ref "USBC") (pin "B1") (pinfunction "GND3_B1") (pintype "passive"))
      (node (ref "USBC") (pin "B12") (pinfunction "GND2_B12") (pintype "passive"))
      (node (ref "USB_BOOT") (pin "2") (pinfunction "S_2") (pintype "passive"))
      (node (ref "X1") (pin "2") (pinfunction "VSS_2") (pintype "power_in"))
      (node (ref "X1") (pin "4") (pinfunction "VDD_4") (pintype "power_in"))
      (node (ref "X2") (pin "2") (pinfunction "VSS_2") (pintype "power_in"))
      (node (ref "X2") (pin "4") (pinfunction "VDD_4") (pintype "power_in"))
    )
    (net (code "15") (name "I2C0_SCL") (class "Default")
      (node (ref "IC2") (pin "7") (pinfunction "GPIO5_7") (pintype "bidirectional"))
      (node (ref "J3") (pin "7") (pinfunction "7_7") (pintype "bidirectional"))
      (node (ref "R38") (pin "1") (pinfunction "1_1") (pintype "passive"))
    )
    (net (code "16") (name "I2C0_SDA") (class "Default")
      (node (ref "IC2") (pin "6") (pinfunction "GPIO4_6") (pintype "bidirectional"))
      (node (ref "J3") (pin "5") (pinfunction "5_5") (pintype "bidirectional"))
      (node (ref "R38") (pin "2") (pinfunction "2_2") (pintype "passive"))
    )
    (net (code "17") (name "I2C1_SCL") (class "Default")
      (node (ref "IC2") (pin "5") (pinfunction "GPIO3_5") (pintype "bidirectional"))
      (node (ref "IC6") (pin "6") (pinfunction "SCL_6") (pintype "bidirectional"))
      (node (ref "R38") (pin "3") (pinfunction "3_3") (pintype "passive"))
    )
    (net (code "18") (name "I2C1_SDA") (class "Default")
      (node (ref "IC2") (pin "4") (pinfunction "GPIO2_4") (pintype "bidirectional"))
      (node (ref "IC6") (pin "5") (pinfunction "SDA_5") (pintype "bidirectional"))
      (node (ref "R38") (pin "4") (pinfunction "4_4") (pintype "passive"))
    )
    (net (code "19") (name "I_MEA{slash}TX") (class "Default")
      (node (ref "IC2") (pin "40") (pinfunction "GPIO28/ADC2_40") (pintype "bidirectional"))
      (node (ref "J1") (pin "4") (pinfunction "4_4") (pintype "bidirectional"))
      (node (ref "R46") (pin "1") (pinfunction "1_1") (pintype "passive"))
    )
    (net (code "20") (name "KEY_0") (class "Default")
      (node (ref "IC2") (pin "15") (pinfunction "GPIO12_15") (pintype "bidirectional"))
      (node (ref "J3") (pin "6") (pinfunction "6_6") (pintype "bidirectional"))
    )
    (net (code "21") (name "KEY_1") (class "Default")
      (node (ref "IC2") (pin "16") (pinfunction "GPIO13_16") (pintype "bidirectional"))
      (node (ref "J3") (pin "8") (pinfunction "8_8") (pintype "bidirectional"))
    )
    (net (code "22") (name "KEY_2") (class "Default")
      (node (ref "IC2") (pin "17") (pinfunction "GPIO14_17") (pintype "bidirectional"))
      (node (ref "J3") (pin "10") (pinfunction "10_10") (pintype "bidirectional"))
    )
    (net (code "23") (name "KEY_3") (class "Default")
      (node (ref "IC2") (pin "18") (pinfunction "GPIO15_18") (pintype "bidirectional"))
      (node (ref "J3") (pin "12") (pinfunction "12_12") (pintype "bidirectional"))
    )
    (net (code "24") (name "Net-(C5-Pad2)") (class "Default")
      (node (ref "C5") (pin "2") (pinfunction "2_2") (pintype "passive"))
      (node (ref "ETH1") (pin "S1") (pinfunction "SHIELD_S1") (pintype "passive"))
      (node (ref "ETH1") (pin "S2") (pinfunction "SHIELD_S2") (pintype "passive"))
    )
    (net (code "25") (name "Net-(C42-Pad1)") (class "Default")
      (node (ref "C42") (pin "1") (pinfunction "1_1") (pintype "passive"))
      (node (ref "R41") (pin "1") (pinfunction "1_1") (pintype "passive"))
    )
    (net (code "26") (name "Net-(C51-Pad1)") (class "Default")
      (node (ref "C51") (pin "1") (pinfunction "1_1") (pintype "passive"))
      (node (ref "R34") (pin "1") (pinfunction "1_1") (pintype "passive"))
    )
    (net (code "27") (name "Net-(ETH1-GK1)") (class "Default")
      (node (ref "ETH1") (pin "10") (pinfunction "GK1_10") (pintype "passive"))
      (node (ref "R9") (pin "2") (pinfunction "2_2") (pintype "passive"))
    )
    (net (code "28") (name "Net-(ETH1-GK2)") (class "Default")
      (node (ref "ETH1") (pin "12") (pinfunction "GK2_12") (pintype "passive"))
      (node (ref "R10") (pin "2") (pinfunction "2_2") (pintype "passive"))
    )
    (net (code "29") (name "Net-(IC1-1V2O)") (class "Default")
      (node (ref "C6") (pin "1") (pinfunction "1_1") (pintype "passive"))
      (node (ref "IC1") (pin "22") (pinfunction "1V2O_22") (pintype "output"))
    )
    (net (code "30") (name "Net-(IC1-EXRES1)") (class "Default")
      (node (ref "IC1") (pin "10") (pinfunction "EXRES1_10") (pintype "bidirectional"))
      (node (ref "R11") (pin "2") (pinfunction "2_2") (pintype "passive"))
    )
    (net (code "31") (name "Net-(IC1-TOCAP)") (class "Default")
      (node (ref "C7") (pin "1") (pinfunction "1_1") (pintype "passive"))
      (node (ref "IC1") (pin "20") (pinfunction "TOCAP_20") (pintype "output"))
    )
    (net (code "32") (name "Net-(IC1-XI)") (class "Default")
      (node (ref "IC1") (pin "30") (pinfunction "XI_30") (pintype "input"))
      (node (ref "R13") (pin "2") (pinfunction "2_2") (pintype "passive"))
    )
    (net (code "33") (name "Net-(IC1-XO)") (class "Default")
      (node (ref "IC1") (pin "31") (pinfunction "XO_31") (pintype "output"))
      (node (ref "R12") (pin "2") (pinfunction "2_2") (pintype "passive"))
    )
    (net (code "34") (name "Net-(IC2-RUN)") (class "Default")
      (node (ref "IC2") (pin "26") (pinfunction "RUN_26") (pintype "bidirectional"))
      (node (ref "R50") (pin "2") (pinfunction "2_2") (pintype "passive"))
      (node (ref "RESET") (pin "1") (pinfunction "P_1") (pintype "passive"))
    )
    (net (code "35") (name "Net-(IC2-USB_DM)") (class "Default")
      (node (ref "IC2") (pin "46") (pinfunction "USB_DM_46") (pintype "bidirectional"))
      (node (ref "R21") (pin "2") (pinfunction "2_2") (pintype "passive"))
    )
    (net (code "36") (name "Net-(IC2-USB_DP)") (class "Default")
      (node (ref "IC2") (pin "47") (pinfunction "USB_DP_47") (pintype "bidirectional"))
      (node (ref "R22") (pin "2") (pinfunction "2_2") (pintype "passive"))
    )
    (net (code "37") (name "Net-(IC3-+IN)") (class "Default")
      (node (ref "C21") (pin "1") (pinfunction "1_1") (pintype "passive"))
      (node (ref "C22") (pin "1") (pinfunction "1_1") (pintype "passive"))
      (node (ref "IC3") (pin "3") (pinfunction "+IN_3") (pintype "input"))
      (node (ref "R17") (pin "1") (pinfunction "1_1") (pintype "passive"))
      (node (ref "REF1") (pin "1") (pinfunction "C_1") (pintype "passive"))
      (node (ref "VREF") (pin "TP") (pinfunction "P$1_TP") (pintype "bidirectional"))
    )
    (net (code "38") (name "Net-(IC5-AAM)") (class "Default")
      (node (ref "IC5") (pin "1") (pinfunction "AAM_1") (pintype "bidirectional"))
      (node (ref "R32") (pin "1") (pinfunction "1_1") (pintype "passive"))
      (node (ref "R45") (pin "2") (pinfunction "2_2") (pintype "passive"))
    )
    (net (code "39") (name "Net-(IC5-BST)") (class "Default")
      (node (ref "IC5") (pin "5") (pinfunction "BST_5") (pintype "bidirectional"))
      (node (ref "R41") (pin "2") (pinfunction "2_2") (pintype "passive"))
    )
    (net (code "40") (name "Net-(IC5-EN)") (class "Default")
      (node (ref "IC5") (pin "6") (pinfunction "EN_6") (pintype "bidirectional"))
      (node (ref "R30") (pin "2") (pinfunction "2_2") (pintype "passive"))
    )
    (net (code "41") (name "Net-(IC5-FB)") (class "Default")
      (node (ref "IC5") (pin "8") (pinfunction "FB_8") (pintype "bidirectional"))
      (node (ref "R42") (pin "1") (pinfunction "1_1") (pintype "passive"))
    )
    (net (code "42") (name "Net-(IC5-SW)") (class "Default")
      (node (ref "C42") (pin "2") (pinfunction "2_2") (pintype "passive"))
      (node (ref "IC5") (pin "3") (pinfunction "SW_3") (pintype "bidirectional"))
      (node (ref "L3") (pin "1") (pinfunction "1_1") (pintype "passive"))
      (node (ref "SW3") (pin "TP") (pinfunction "P$1_TP") (pintype "bidirectional"))
    )
    (net (code "43") (name "Net-(IC5-VCC)") (class "Default")
      (node (ref "C40") (pin "1") (pinfunction "1_1") (pintype "passive"))
      (node (ref "IC5") (pin "7") (pinfunction "VCC_7") (pintype "bidirectional"))
      (node (ref "R45") (pin "1") (pinfunction "1_1") (pintype "passive"))
    )
    (net (code "44") (name "Net-(IC6-A0)") (class "Default")
      (node (ref "IC6") (pin "1") (pinfunction "A0_1") (pintype "bidirectional"))
      (node (ref "R27") (pin "1") (pinfunction "1_1") (pintype "passive"))
      (node (ref "R28") (pin "2") (pinfunction "2_2") (pintype "passive"))
    )
    (net (code "45") (name "Net-(IC7-AAM)") (class "Default")
      (node (ref "IC7") (pin "1") (pinfunction "AAM_1") (pintype "bidirectional"))
      (node (ref "R29") (pin "2") (pinfunction "2_2") (pintype "passive"))
      (node (ref "R33") (pin "1") (pinfunction "1_1") (pintype "passive"))
    )
    (net (code "46") (name "Net-(IC7-BST)") (class "Default")
      (node (ref "IC7") (pin "5") (pinfunction "BST_5") (pintype "bidirectional"))
      (node (ref "R34") (pin "2") (pinfunction "2_2") (pintype "passive"))
    )
    (net (code "47") (name "Net-(IC7-EN)") (class "Default")
      (node (ref "IC7") (pin "6") (pinfunction "EN_6") (pintype "bidirectional"))
      (node (ref "R31") (pin "2") (pinfunction "2_2") (pintype "passive"))
    )
    (net (code "48") (name "Net-(IC7-FB)") (class "Default")
      (node (ref "IC7") (pin "8") (pinfunction "FB_8") (pintype "bidirectional"))
      (node (ref "R35") (pin "1") (pinfunction "1_1") (pintype "passive"))
    )
    (net (code "49") (name "Net-(IC7-SW)") (class "Default")
      (node (ref "C51") (pin "2") (pinfunction "2_2") (pintype "passive"))
      (node (ref "IC7") (pin "3") (pinfunction "SW_3") (pintype "bidirectional"))
      (node (ref "L2") (pin "1") (pinfunction "1_1") (pintype "passive"))
      (node (ref "SW5") (pin "TP") (pinfunction "P$1_TP") (pintype "bidirectional"))
    )
    (net (code "50") (name "Net-(IC7-VCC)") (class "Default")
      (node (ref "C49") (pin "1") (pinfunction "1_1") (pintype "passive"))
      (node (ref "IC7") (pin "7") (pinfunction "VCC_7") (pintype "bidirectional"))
      (node (ref "R29") (pin "1") (pinfunction "1_1") (pintype "passive"))
    )
    (net (code "51") (name "Net-(VFB3-P$1)") (class "Default")
      (node (ref "C43") (pin "2") (pinfunction "2_2") (pintype "passive"))
      (node (ref "R42") (pin "2") (pinfunction "2_2") (pintype "passive"))
      (node (ref "R43") (pin "2") (pinfunction "2_2") (pintype "passive"))
      (node (ref "R44") (pin "1") (pinfunction "1_1") (pintype "passive"))
      (node (ref "VFB3") (pin "TP") (pinfunction "P$1_TP") (pintype "bidirectional"))
    )
    (net (code "52") (name "Net-(VFB5-P$1)") (class "Default")
      (node (ref "C52") (pin "2") (pinfunction "2_2") (pintype "passive"))
      (node (ref "R35") (pin "2") (pinfunction "2_2") (pintype "passive"))
      (node (ref "R36") (pin "2") (pinfunction "2_2") (pintype "passive"))
      (node (ref "R37") (pin "1") (pinfunction "1_1") (pintype "passive"))
      (node (ref "VFB5") (pin "TP") (pinfunction "P$1_TP") (pintype "bidirectional"))
    )
    (net (code "53") (name "Net-(X1-CON)") (class "Default")
      (node (ref "C8") (pin "1") (pinfunction "1_1") (pintype "passive"))
      (node (ref "R12") (pin "1") (pinfunction "1_1") (pintype "passive"))
      (node (ref "X1") (pin "1") (pinfunction "CON_1") (pintype "input"))
    )
    (net (code "54") (name "Net-(X1-OUT)") (class "Default")
      (node (ref "C9") (pin "1") (pinfunction "1_1") (pintype "passive"))
      (node (ref "R13") (pin "1") (pinfunction "1_1") (pintype "passive"))
      (node (ref "X1") (pin "3") (pinfunction "OUT_3") (pintype "output"))
    )
    (net (code "55") (name "Net-(X2-OUT)") (class "Default")
      (node (ref "C20") (pin "1") (pinfunction "1_1") (pintype "passive"))
      (node (ref "R15") (pin "2") (pinfunction "2_2") (pintype "passive"))
      (node (ref "R16") (pin "1") (pinfunction "1_1") (pintype "passive"))
      (node (ref "X2") (pin "3") (pinfunction "OUT_3") (pintype "output"))
    )
    (net (code "56") (name "PWR_DETECT") (class "Default")
      (node (ref "12VFB") (pin "TP") (pinfunction "P$1_TP") (pintype "bidirectional"))
      (node (ref "IC2") (pin "41") (pinfunction "GPIO29/ADC3_41") (pintype "bidirectional"))
      (node (ref "R48") (pin "1") (pinfunction "1_1") (pintype "passive"))
      (node (ref "R49") (pin "2") (pinfunction "2_2") (pintype "passive"))
    )
    (net (code "57") (name "QSPI_SCLK") (class "Default")
      (node (ref "IC2") (pin "52") (pinfunction "QSPI_SCLK_52") (pintype "bidirectional"))
      (node (ref "IC4") (pin "6") (pinfunction "CLK_6") (pintype "bidirectional"))
    )
    (net (code "58") (name "QSPI_SD0") (class "Default")
      (node (ref "IC2") (pin "53") (pinfunction "QSPI_SD0_53") (pintype "bidirectional"))
      (node (ref "IC4") (pin "5") (pinfunction "DI/IO0_5") (pintype "bidirectional"))
    )
    (net (code "59") (name "QSPI_SD1") (class "Default")
      (node (ref "IC2") (pin "55") (pinfunction "QSPI_SD1_55") (pintype "bidirectional"))
      (node (ref "IC4") (pin "2") (pinfunction "DO/IO1_2") (pintype "bidirectional"))
    )
    (net (code "60") (name "QSPI_SD2") (class "Default")
      (node (ref "IC2") (pin "54") (pinfunction "QSPI_SD2_54") (pintype "bidirectional"))
      (node (ref "IC4") (pin "3") (pinfunction "~{WP}/IO2_3") (pintype "bidirectional"))
    )
    (net (code "61") (name "QSPI_SD3") (class "Default")
      (node (ref "IC2") (pin "51") (pinfunction "QSPI_SD3_51") (pintype "bidirectional"))
      (node (ref "IC4") (pin "7") (pinfunction "~{HOLD}/IO3_7") (pintype "bidirectional"))
    )
    (net (code "62") (name "RCT") (class "Default")
      (node (ref "C1") (pin "1") (pinfunction "1_1") (pintype "passive"))
      (node (ref "ETH1") (pin "5") (pinfunction "RCT_5") (pintype "passive"))
      (node (ref "R5") (pin "1") (pinfunction "1_1") (pintype "passive"))
      (node (ref "R6") (pin "1") (pinfunction "1_1") (pintype "passive"))
    )
    (net (code "63") (name "RDC_RD_N") (class "Default")
      (node (ref "C3") (pin "1") (pinfunction "1_1") (pintype "passive"))
      (node (ref "R4") (pin "2") (pinfunction "2_2") (pintype "passive"))
      (node (ref "R5") (pin "2") (pinfunction "2_2") (pintype "passive"))
    )
    (net (code "64") (name "RDC_RD_P") (class "Default")
      (node (ref "C4") (pin "1") (pinfunction "1_1") (pintype "passive"))
      (node (ref "R3") (pin "2") (pinfunction "2_2") (pintype "passive"))
      (node (ref "R6") (pin "2") (pinfunction "2_2") (pintype "passive"))
    )
    (net (code "65") (name "RD_N") (class "Default")
      (node (ref "C3") (pin "2") (pinfunction "2_2") (pintype "passive"))
      (node (ref "ETH1") (pin "6") (pinfunction "RD-_6") (pintype "passive"))
    )
    (net (code "66") (name "RD_P") (class "Default")
      (node (ref "C4") (pin "2") (pinfunction "2_2") (pintype "passive"))
      (node (ref "ETH1") (pin "4") (pinfunction "RD+_4") (pintype "passive"))
    )
    (net (code "67") (name "REL_0") (class "Default")
      (node (ref "IC8") (pin "15") (pinfunction "GPA0_15") (pintype "bidirectional"))
      (node (ref "J1") (pin "12") (pinfunction "12_12") (pintype "bidirectional"))
    )
    (net (code "68") (name "REL_1") (class "Default")
      (node (ref "IC8") (pin "16") (pinfunction "GPA1_16") (pintype "bidirectional"))
      (node (ref "J1") (pin "11") (pinfunction "11_11") (pintype "bidirectional"))
    )
    (net (code "69") (name "REL_2") (class "Default")
      (node (ref "IC8") (pin "17") (pinfunction "GPA2_17") (pintype "bidirectional"))
      (node (ref "J1") (pin "10") (pinfunction "10_10") (pintype "bidirectional"))
    )
    (net (code "70") (name "REL_3") (class "Default")
      (node (ref "IC8") (pin "18") (pinfunction "GPA3_18") (pintype "bidirectional"))
      (node (ref "J1") (pin "9") (pinfunction "9_9") (pintype "bidirectional"))
    )
    (net (code "71") (name "REL_4") (class "Default")
      (node (ref "IC8") (pin "19") (pinfunction "GPA4_19") (pintype "bidirectional"))
      (node (ref "J1") (pin "8") (pinfunction "8_8") (pintype "bidirectional"))
    )
    (net (code "72") (name "REL_5") (class "Default")
      (node (ref "IC8") (pin "20") (pinfunction "GPA5_20") (pintype "bidirectional"))
      (node (ref "J1") (pin "7") (pinfunction "7_7") (pintype "bidirectional"))
    )
    (net (code "73") (name "REL_6") (class "Default")
      (node (ref "IC8") (pin "21") (pinfunction "GPA6_21") (pintype "bidirectional"))
      (node (ref "J1") (pin "6") (pinfunction "6_6") (pintype "bidirectional"))
    )
    (net (code "74") (name "REL_7") (class "Default")
      (node (ref "IC8") (pin "22") (pinfunction "GPA7_22") (pintype "bidirectional"))
      (node (ref "J1") (pin "5") (pinfunction "5_5") (pintype "bidirectional"))
    )
    (net (code "75") (name "RP_XI") (class "Default")
      (node (ref "C19") (pin "1") (pinfunction "1_1") (pintype "passive"))
      (node (ref "IC2") (pin "20") (pinfunction "XIN_20") (pintype "bidirectional"))
      (node (ref "R15") (pin "1") (pinfunction "1_1") (pintype "passive"))
      (node (ref "X2") (pin "1") (pinfunction "CON_1") (pintype "input"))
    )
    (net (code "76") (name "RP_XO") (class "Default")
      (node (ref "IC2") (pin "21") (pinfunction "XOUT_21") (pintype "bidirectional"))
      (node (ref "R16") (pin "2") (pinfunction "2_2") (pintype "passive"))
    )
    (net (code "77") (name "RX_RD_N") (class "Default")
      (node (ref "IC1") (pin "5") (pinfunction "RXN_5") (pintype "input"))
      (node (ref "R4") (pin "1") (pinfunction "1_1") (pintype "passive"))
    )
    (net (code "78") (name "RX_RD_P") (class "Default")
      (node (ref "IC1") (pin "6") (pinfunction "RXP_6") (pintype "input"))
      (node (ref "R3") (pin "1") (pinfunction "1_1") (pintype "passive"))
    )
    (net (code "79") (name "SPI0_MISO") (class "Default")
      (node (ref "IC1") (pin "34") (pinfunction "MISO_34") (pintype "output"))
      (node (ref "IC2") (pin "27") (pinfunction "GPIO16_27") (pintype "bidirectional"))
    )
    (net (code "80") (name "SPI0_MOSI") (class "Default")
      (node (ref "IC1") (pin "35") (pinfunction "MOSI_35") (pintype "input"))
      (node (ref "IC2") (pin "30") (pinfunction "GPIO19_30") (pintype "bidirectional"))
    )
    (net (code "81") (name "SPI0_SCK") (class "Default")
      (node (ref "IC1") (pin "33") (pinfunction "SCLK_33") (pintype "input"))
      (node (ref "IC2") (pin "29") (pinfunction "GPIO18_29") (pintype "bidirectional"))
    )
    (net (code "82") (name "SPI1_MISO") (class "Default")
      (node (ref "IC2") (pin "11") (pinfunction "GPIO8_11") (pintype "bidirectional"))
      (node (ref "IC8") (pin "12") (pinfunction "SO_12") (pintype "output"))
      (node (ref "J2") (pin "7") (pinfunction "7_7") (pintype "bidirectional"))
    )
    (net (code "83") (name "SPI1_MOSI") (class "Default")
      (node (ref "IC2") (pin "14") (pinfunction "GPIO11_14") (pintype "bidirectional"))
      (node (ref "IC8") (pin "11") (pinfunction "SI_11") (pintype "input"))
      (node (ref "J2") (pin "5") (pinfunction "5_5") (pintype "bidirectional"))
    )
    (net (code "84") (name "SPI1_SCK") (class "Default")
      (node (ref "IC2") (pin "13") (pinfunction "GPIO10_13") (pintype "bidirectional"))
      (node (ref "IC8") (pin "10") (pinfunction "SCK_10") (pintype "input"))
      (node (ref "J2") (pin "9") (pinfunction "9_9") (pintype "bidirectional"))
    )
    (net (code "85") (name "SWCLK") (class "Default")
      (node (ref "DBG2") (pin "1") (pinfunction "P$1_1") (pintype "bidirectional"))
      (node (ref "IC2") (pin "24") (pinfunction "SWCLK_24") (pintype "bidirectional"))
    )
    (net (code "86") (name "SWDIO") (class "Default")
      (node (ref "DBG2") (pin "3") (pinfunction "P$3_3") (pintype "bidirectional"))
      (node (ref "IC2") (pin "25") (pinfunction "SWDIO_25") (pintype "bidirectional"))
    )
    (net (code "87") (name "TCT") (class "Default")
      (node (ref "C2") (pin "1") (pinfunction "1_1") (pintype "passive"))
      (node (ref "ETH1") (pin "2") (pinfunction "TCT_2") (pintype "passive"))
      (node (ref "R40") (pin "1") (pinfunction "1_1") (pintype "passive"))
    )
    (net (code "88") (name "TD_N") (class "Default")
      (node (ref "ETH1") (pin "3") (pinfunction "TD-_3") (pintype "passive"))
      (node (ref "R1") (pin "2") (pinfunction "2_2") (pintype "passive"))
      (node (ref "R8") (pin "1") (pinfunction "1_1") (pintype "passive"))
    )
    (net (code "89") (name "TD_P") (class "Default")
      (node (ref "ETH1") (pin "1") (pinfunction "TD+_1") (pintype "passive"))
      (node (ref "R2") (pin "2") (pinfunction "2_2") (pintype "passive"))
      (node (ref "R7") (pin "1") (pinfunction "1_1") (pintype "passive"))
    )
    (net (code "90") (name "TX_TD_N") (class "Default")
      (node (ref "IC1") (pin "1") (pinfunction "TXN_1") (pintype "output"))
      (node (ref "R1") (pin "1") (pinfunction "1_1") (pintype "passive"))
    )
    (net (code "91") (name "TX_TD_P") (class "Default")
      (node (ref "IC1") (pin "2") (pinfunction "TXP_2") (pintype "output"))
      (node (ref "R2") (pin "1") (pinfunction "1_1") (pintype "passive"))
    )
    (net (code "92") (name "UART0_RX") (class "Default")
      (node (ref "DBG1") (pin "1") (pinfunction "P$1_1") (pintype "bidirectional"))
      (node (ref "IC2") (pin "2") (pinfunction "GPIO0_2") (pintype "bidirectional"))
      (node (ref "R47") (pin "2") (pinfunction "2_2") (pintype "passive"))
    )
    (net (code "93") (name "UART0_TX") (class "Default")
      (node (ref "DBG1") (pin "3") (pinfunction "P$3_3") (pintype "bidirectional"))
      (node (ref "IC2") (pin "3") (pinfunction "GPIO1_3") (pintype "bidirectional"))
      (node (ref "R46") (pin "2") (pinfunction "2_2") (pintype "passive"))
    )
    (net (code "94") (name "USB_BOOT") (class "Default")
      (node (ref "R19") (pin "1") (pinfunction "1_1") (pintype "passive"))
      (node (ref "USB_BOOT") (pin "1") (pinfunction "P_1") (pintype "passive"))
    )
    (net (code "95") (name "USB_SHIELD") (class "Default")
      (node (ref "C54") (pin "1") (pinfunction "1_1") (pintype "passive"))
      (node (ref "R39") (pin "1") (pinfunction "1_1") (pintype "passive"))
      (node (ref "USBC") (pin "S1") (pinfunction "SHIELD_S1") (pintype "passive"))
      (node (ref "USBC") (pin "S2") (pinfunction "SHIELD_S2") (pintype "passive"))
      (node (ref "USBC") (pin "S3") (pinfunction "SHIELD_S3") (pintype "passive"))
      (node (ref "USBC") (pin "S4") (pinfunction "SHIELD_S4") (pintype "passive"))
    )
    (net (code "96") (name "VBUS") (class "Default")
      (node (ref "C26") (pin "1") (pinfunction "1_1") (pintype "passive"))
      (node (ref "C27") (pin "1") (pinfunction "1_1") (pintype "passive"))
      (node (ref "ESD1") (pin "4") (pinfunction "C3_4") (pintype "bidirectional"))
      (node (ref "R20") (pin "1") (pinfunction "1_1") (pintype "passive"))
      (node (ref "R25") (pin "1") (pinfunction "1_1") (pintype "passive"))
      (node (ref "USBC") (pin "A4") (pinfunction "VBUS_A4") (pintype "passive"))
      (node (ref "USBC") (pin "A9") (pinfunction "VBUS1_A9") (pintype "passive"))
      (node (ref "USBC") (pin "B4") (pinfunction "VBUS3_B4") (pintype "passive"))
      (node (ref "USBC") (pin "B9") (pinfunction "VBUS2_B9") (pintype "passive"))
      (node (ref "VBUS") (pin "TP") (pinfunction "P$1_TP") (pintype "bidirectional"))
    )
    (net (code "97") (name "V_MEA{slash}RX") (class "Default")
      (node (ref "IC2") (pin "39") (pinfunction "GPIO27/ADC1_39") (pintype "bidirectional"))
      (node (ref "J1") (pin "3") (pinfunction "3_3") (pintype "bidirectional"))
      (node (ref "R47") (pin "1") (pinfunction "1_1") (pintype "passive"))
    )
    (net (code "98") (name "V_USB") (class "Default")
      (node (ref "IC2") (pin "38") (pinfunction "GPIO26/ADC0_38") (pintype "bidirectional"))
      (node (ref "R25") (pin "2") (pinfunction "2_2") (pintype "passive"))
      (node (ref "R26") (pin "1") (pinfunction "1_1") (pintype "passive"))
    )
    (net (code "99") (name "unconnected-(IC1-DNC-Pad7)") (class "Default")
      (node (ref "IC1") (pin "7") (pinfunction "DNC_7") (pintype "bidirectional"))
    )
    (net (code "100") (name "unconnected-(IC1-DUPLED-Pad26)") (class "Default")
      (node (ref "IC1") (pin "26") (pinfunction "DUPLED_26") (pintype "output"))
    )
    (net (code "101") (name "unconnected-(IC1-RSVD1-Pad23)") (class "Default")
      (node (ref "IC1") (pin "23") (pinfunction "RSVD1_23") (pintype "input"))
    )
    (net (code "102") (name "unconnected-(IC1-RSVD2-Pad38)") (class "Default")
      (node (ref "IC1") (pin "38") (pinfunction "RSVD2_38") (pintype "input"))
    )
    (net (code "103") (name "unconnected-(IC1-RSVD3-Pad39)") (class "Default")
      (node (ref "IC1") (pin "39") (pinfunction "RSVD3_39") (pintype "input"))
    )
    (net (code "104") (name "unconnected-(IC1-RSVD4-Pad40)") (class "Default")
      (node (ref "IC1") (pin "40") (pinfunction "RSVD4_40") (pintype "input"))
    )
    (net (code "105") (name "unconnected-(IC1-RSVD5-Pad41)") (class "Default")
      (node (ref "IC1") (pin "41") (pinfunction "RSVD5_41") (pintype "input"))
    )
    (net (code "106") (name "unconnected-(IC1-RSVD6-Pad42)") (class "Default")
      (node (ref "IC1") (pin "42") (pinfunction "RSVD6_42") (pintype "input"))
    )
    (net (code "107") (name "unconnected-(IC1-SPDLED-Pad24)") (class "Default")
      (node (ref "IC1") (pin "24") (pinfunction "SPDLED_24") (pintype "output"))
    )
    (net (code "108") (name "unconnected-(IC1-VBG-Pad18)") (class "Default")
      (node (ref "IC1") (pin "18") (pinfunction "VBG_18") (pintype "output"))
    )
    (net (code "109") (name "unconnected-(IC2-GPIO24-Pad36)") (class "Default")
      (node (ref "IC2") (pin "36") (pinfunction "GPIO24_36") (pintype "bidirectional"))
    )
    (net (code "110") (name "unconnected-(IC2-GPIO25-Pad37)") (class "Default")
      (node (ref "IC2") (pin "37") (pinfunction "GPIO25_37") (pintype "bidirectional"))
    )
    (net (code "111") (name "unconnected-(IC8-GPB0-Pad24)") (class "Default")
      (node (ref "IC8") (pin "24") (pinfunction "GPB0_24") (pintype "bidirectional"))
    )
    (net (code "112") (name "unconnected-(IC8-GPB1-Pad1)") (class "Default")
      (node (ref "IC8") (pin "1") (pinfunction "GPB1_1") (pintype "bidirectional"))
    )
    (net (code "113") (name "unconnected-(IC8-GPB2-Pad2)") (class "Default")
      (node (ref "IC8") (pin "2") (pinfunction "GPB2_2") (pintype "bidirectional"))
    )
    (net (code "114") (name "unconnected-(IC8-GPB3-Pad3)") (class "Default")
      (node (ref "IC8") (pin "3") (pinfunction "GPB3_3") (pintype "bidirectional"))
    )
    (net (code "115") (name "unconnected-(IC8-GPB4-Pad4)") (class "Default")
      (node (ref "IC8") (pin "4") (pinfunction "GPB4_4") (pintype "bidirectional"))
    )
    (net (code "116") (name "unconnected-(IC8-GPB5-Pad5)") (class "Default")
      (node (ref "IC8") (pin "5") (pinfunction "GPB5_5") (pintype "bidirectional"))
    )
    (net (code "117") (name "unconnected-(IC8-GPB6-Pad6)") (class "Default")
      (node (ref "IC8") (pin "6") (pinfunction "GPB6_6") (pintype "bidirectional"))
    )
    (net (code "118") (name "unconnected-(IC8-GPB7-Pad7)") (class "Default")
      (node (ref "IC8") (pin "7") (pinfunction "GPB7_7") (pintype "bidirectional"))
    )
    (net (code "119") (name "unconnected-(IC8-INTA-Pad14)") (class "Default")
      (node (ref "IC8") (pin "14") (pinfunction "INTA_14") (pintype "output"))
    )
    (net (code "120") (name "unconnected-(J2-Pad6)") (class "Default")
      (node (ref "J2") (pin "6") (pinfunction "6_6") (pintype "bidirectional"))
    )
    (net (code "121") (name "unconnected-(J2-Pad8)") (class "Default")
      (node (ref "J2") (pin "8") (pinfunction "8_8") (pintype "bidirectional"))
    )
    (net (code "122") (name "unconnected-(J2-Pad10)") (class "Default")
      (node (ref "J2") (pin "10") (pinfunction "10_10") (pintype "bidirectional"))
    )
    (net (code "123") (name "unconnected-(J2-Pad12)") (class "Default")
      (node (ref "J2") (pin "12") (pinfunction "12_12") (pintype "bidirectional"))
    )
    (net (code "124") (name "unconnected-(USBC-SBU1-PadA8)") (class "Default")
      (node (ref "USBC") (pin "A8") (pinfunction "SBU1_A8") (pintype "passive"))
    )
    (net (code "125") (name "unconnected-(USBC-SBU2-PadB8)") (class "Default")
      (node (ref "USBC") (pin "B8") (pinfunction "SBU2_B8") (pintype "passive"))
    )
    (net (code "126") (name "~{ACT}") (class "Default")
      (node (ref "IC1") (pin "27") (pinfunction "ACTLED_27") (pintype "output"))
      (node (ref "R10") (pin "1") (pinfunction "1_1") (pintype "passive"))
    )
    (net (code "127") (name "~{INT}") (class "Default")
      (node (ref "IC1") (pin "36") (pinfunction "~{INTN}_36") (pintype "input"))
      (node (ref "IC2") (pin "32") (pinfunction "GPIO21_32") (pintype "bidirectional"))
    )
    (net (code "128") (name "~{LINK}") (class "Default")
      (node (ref "IC1") (pin "25") (pinfunction "LINKLED_25") (pintype "output"))
      (node (ref "R9") (pin "1") (pinfunction "1_1") (pintype "passive"))
    )
    (net (code "129") (name "~{QSPI_SS}") (class "Default")
      (node (ref "IC2") (pin "56") (pinfunction "QSPI_SS_N_56") (pintype "bidirectional"))
      (node (ref "IC4") (pin "1") (pinfunction "~{CS}_1") (pintype "bidirectional"))
      (node (ref "R18") (pin "1") (pinfunction "1_1") (pintype "passive"))
      (node (ref "R19") (pin "2") (pinfunction "2_2") (pintype "passive"))
    )
    (net (code "130") (name "~{RST}") (class "Default")
      (node (ref "IC1") (pin "37") (pinfunction "~{RSTN}_37") (pintype "input"))
      (node (ref "IC2") (pin "31") (pinfunction "GPIO20_31") (pintype "bidirectional"))
      (node (ref "R14") (pin "1") (pinfunction "1_1") (pintype "passive"))
    )
    (net (code "131") (name "~{SPI0_CS}") (class "Default")
      (node (ref "IC1") (pin "32") (pinfunction "~{SCSN}_32") (pintype "input"))
      (node (ref "IC2") (pin "28") (pinfunction "GPIO17_28") (pintype "bidirectional"))
    )
    (net (code "132") (name "~{SPI1_CS_S}") (class "Default")
      (node (ref "IC2") (pin "8") (pinfunction "GPIO6_8") (pintype "bidirectional"))
      (node (ref "J2") (pin "11") (pinfunction "11_11") (pintype "bidirectional"))
    )
    (net (code "133") (name "~{SPI1_CS}") (class "Default")
      (node (ref "IC2") (pin "12") (pinfunction "GPIO9_12") (pintype "bidirectional"))
      (node (ref "IC8") (pin "9") (pinfunction "~{CS}_9") (pintype "input"))
    )
  )
)
